# SDA390V1_TASLAK.net
KiCad netlist of a schematic drawn in EAGLE
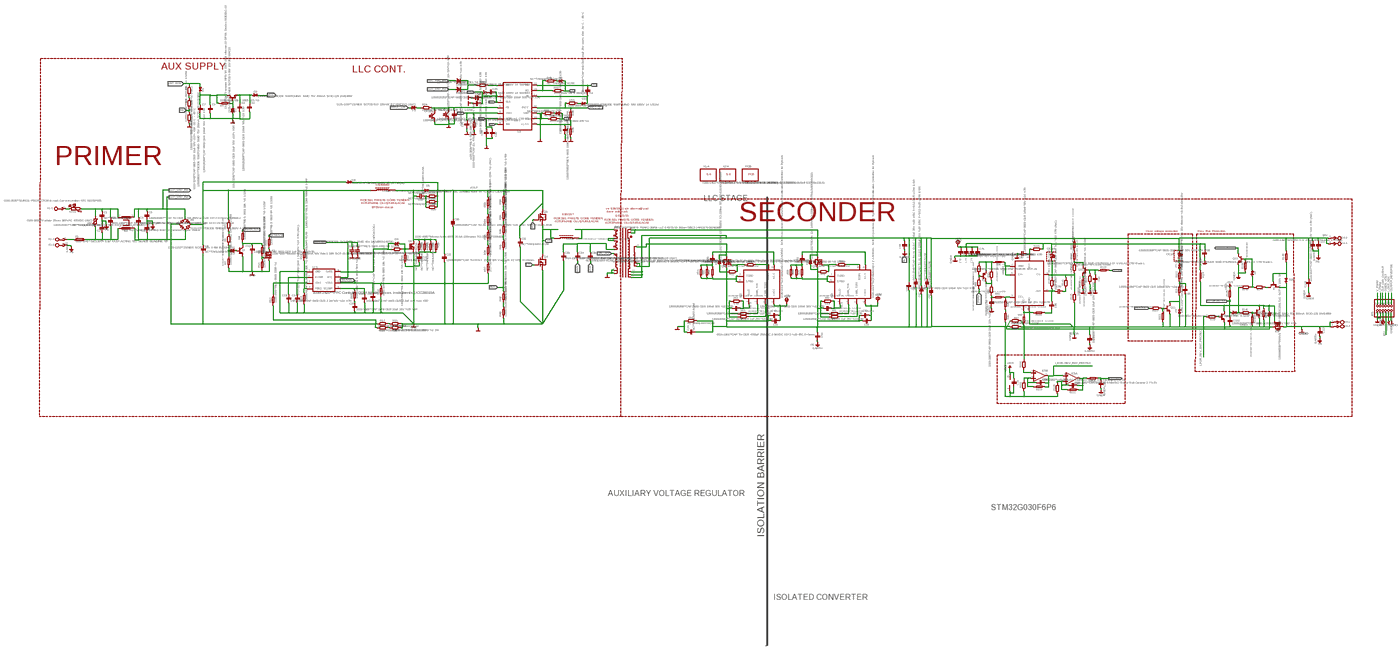
[diagram p0: schematic, sheet 1, overview]
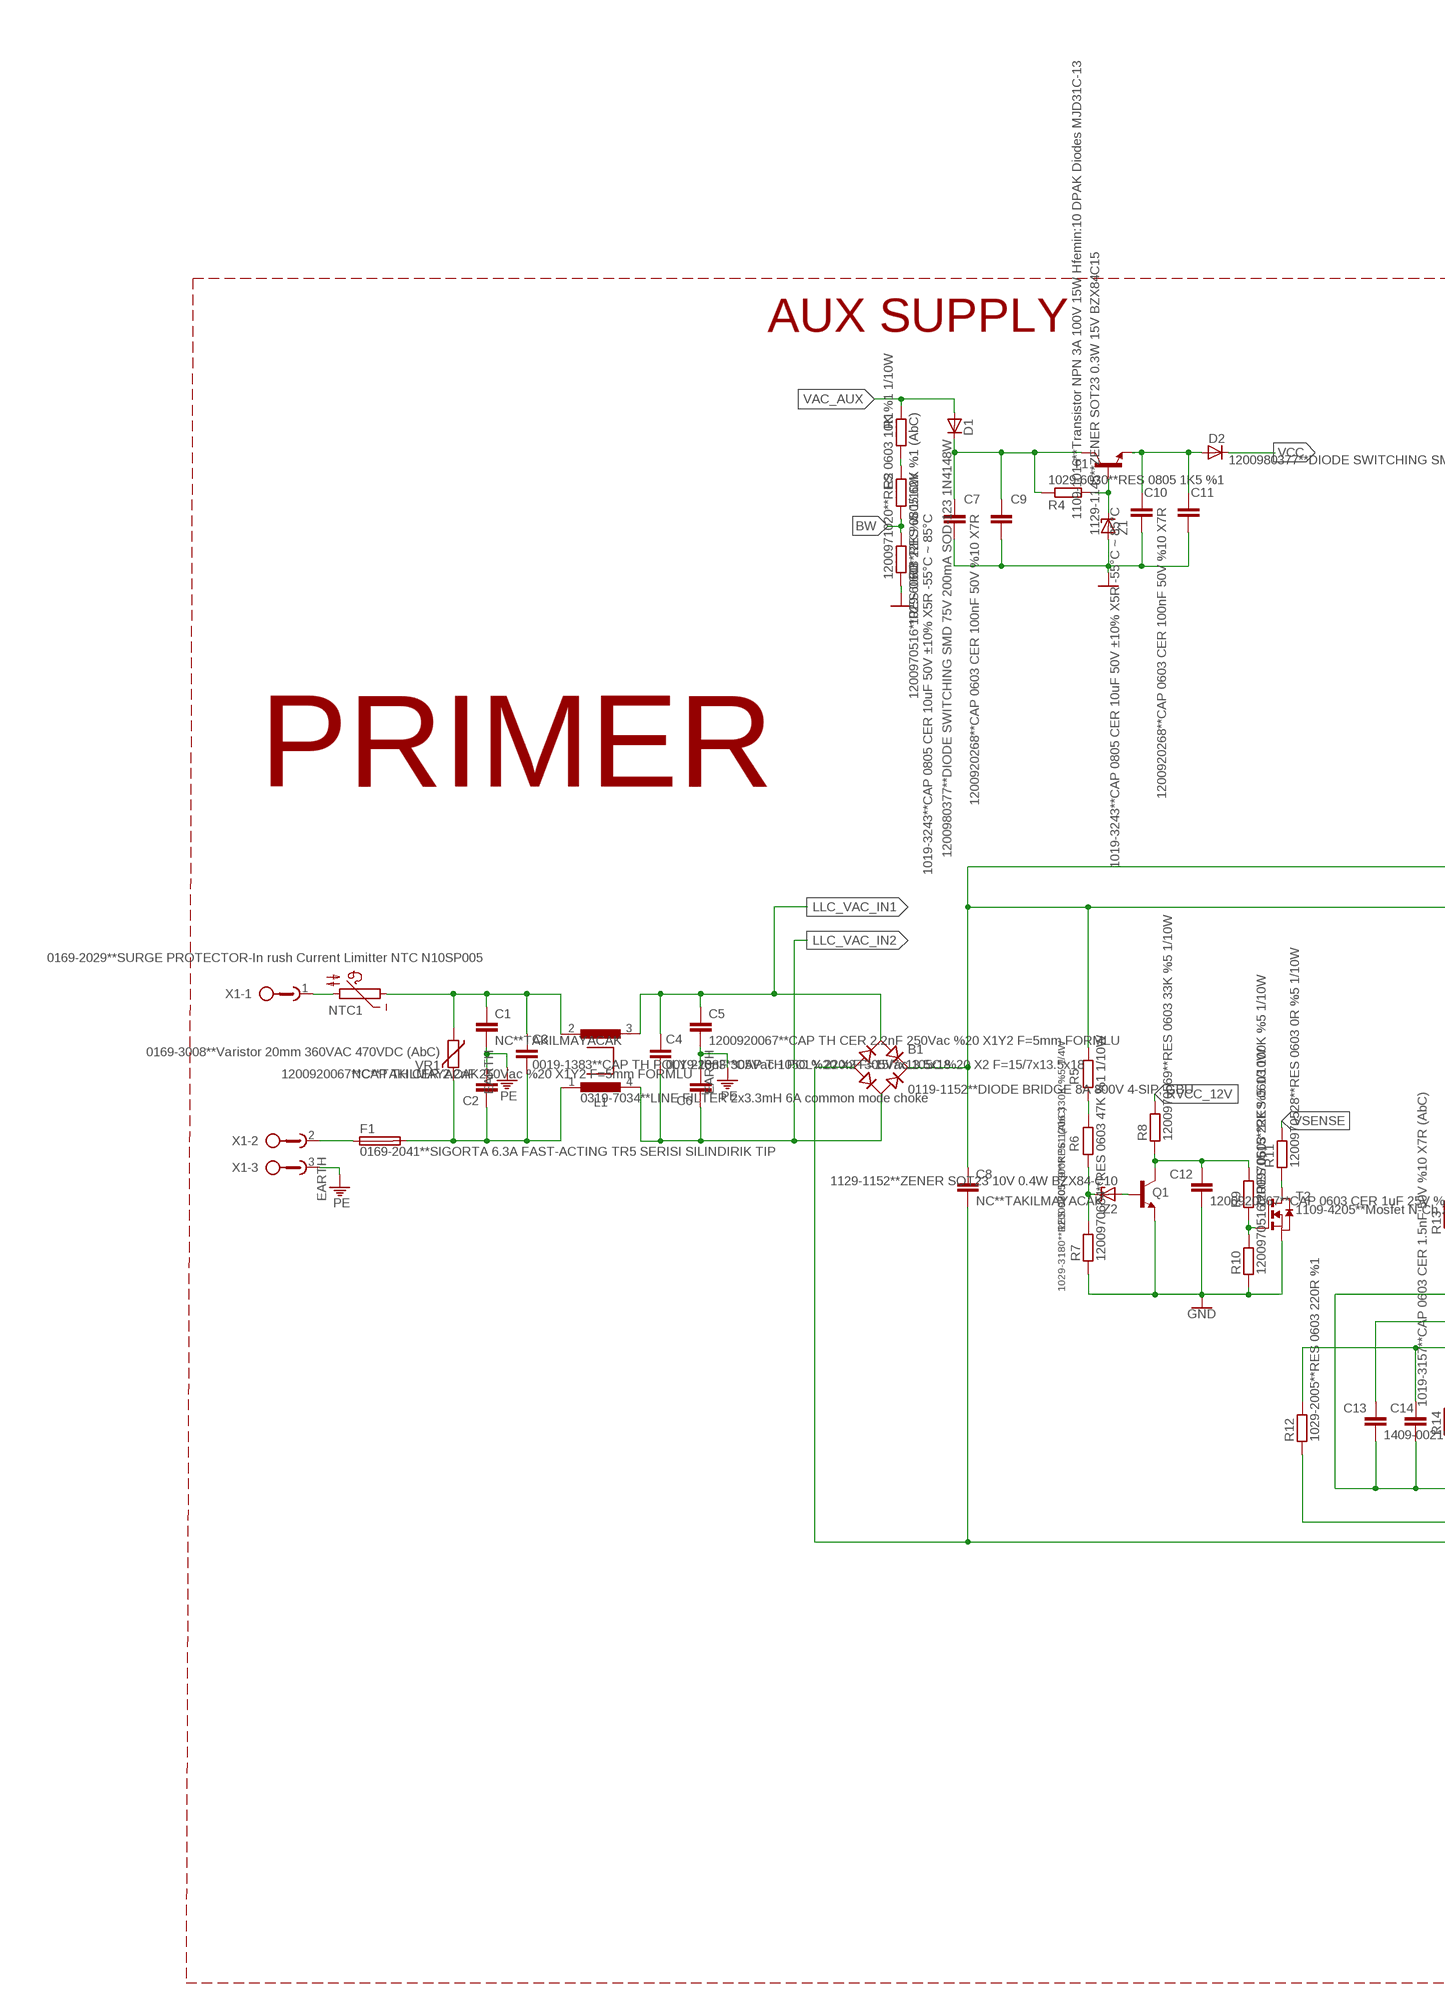
[diagram p1: schematic, sheet 1, part 1 of 4]
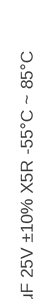
[diagram p2: schematic, sheet 1, part 2 of 4]
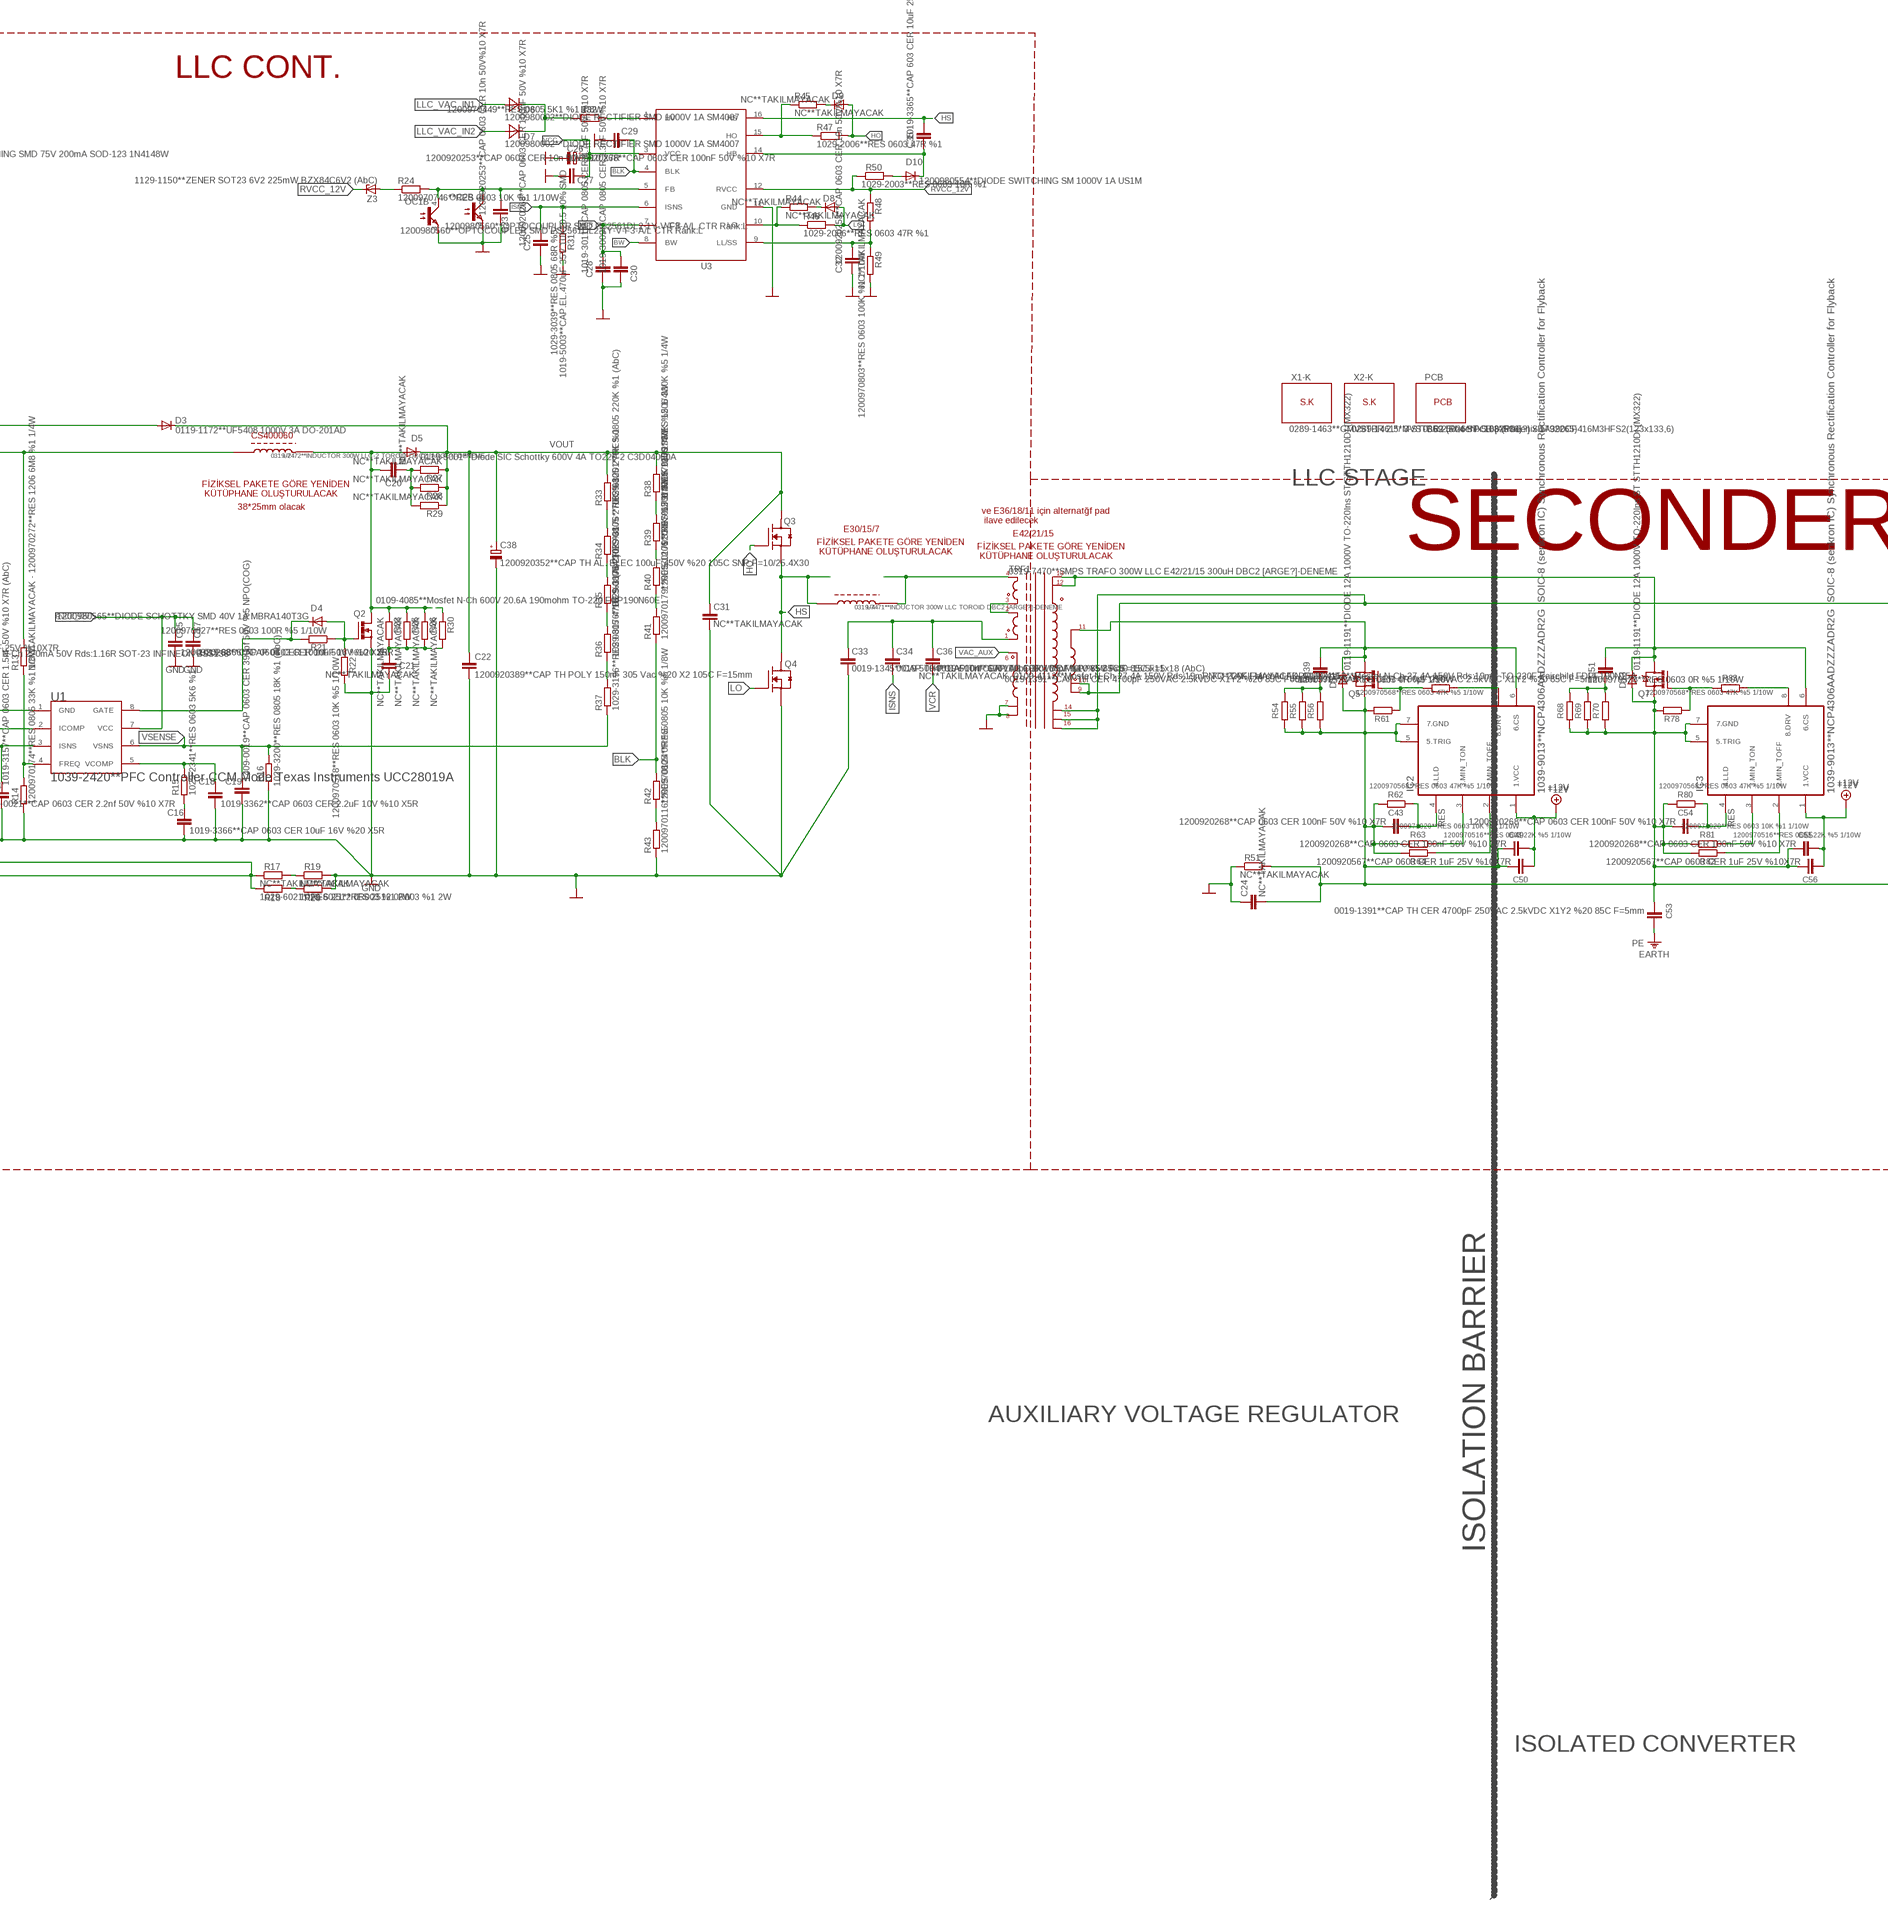
[diagram p3: schematic, sheet 1, part 3 of 4]
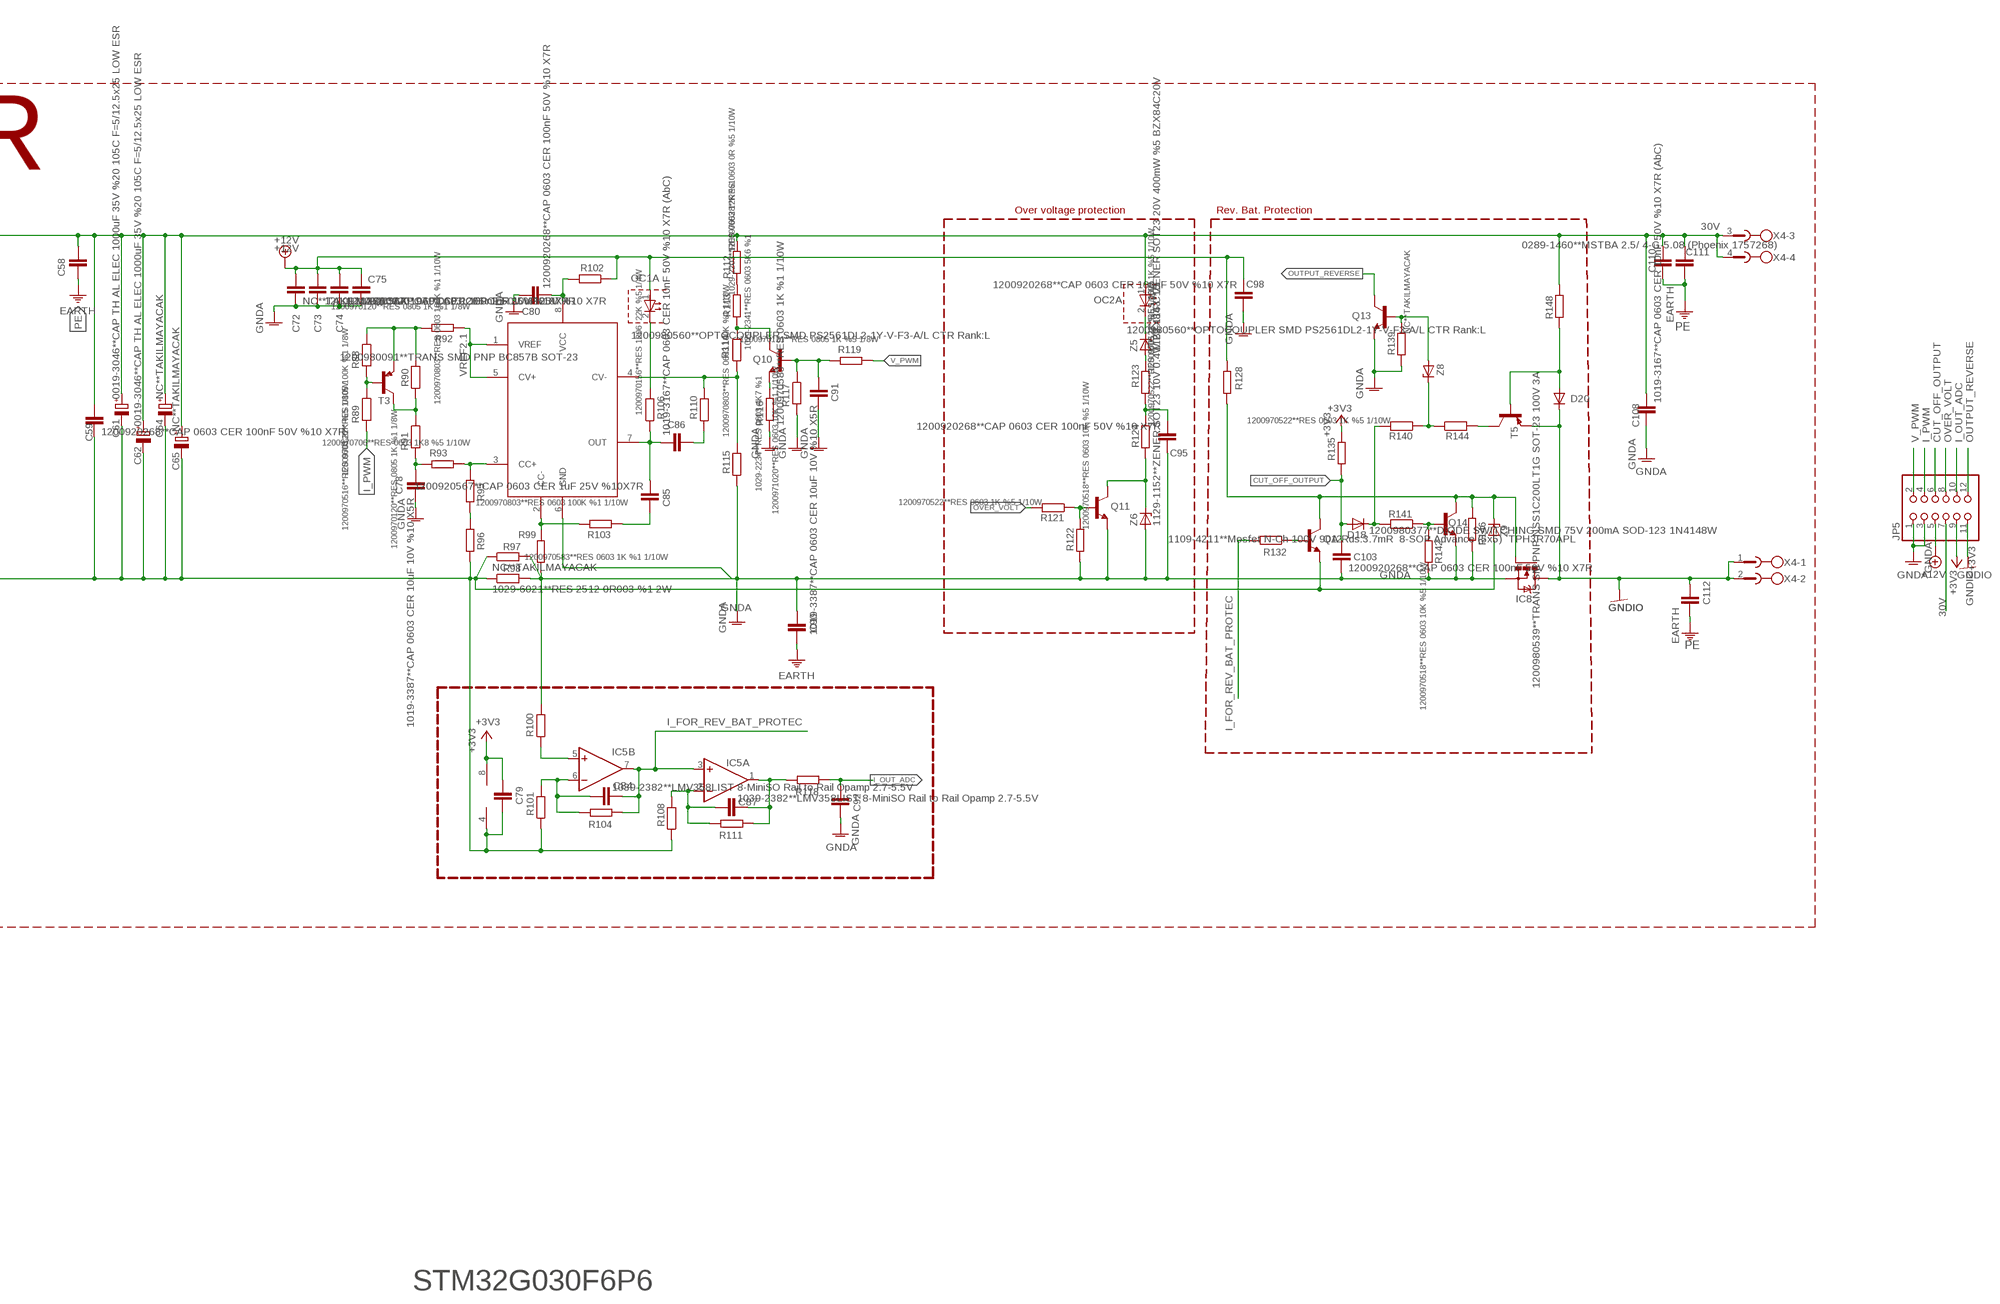
[diagram p4: schematic, sheet 1, part 4 of 4]

(export (version "E")
  (design (tool "Eeschema 10.0.6"))
  (components
    (comp (ref "B1")
      (value "0119-1152**DIODE BRIDGE 8A 800V 4-SIP, GBU")
      (footprint "eagle-import:DıODE_BRIDGE_8A_DIK")
      (libsource (lib "eagle-import") (part "DıODE_BRIDGE_8A_DIK"))
    )
    (comp (ref "C1")
      (value "NC**TAKILMAYACAK")
      (footprint "eagle-import:C050-035X075")
      (libsource (lib "eagle-import") (part "C-EU050-035X075"))
    )
    (comp (ref "C2")
      (value "NC**TAKILMAYACAK")
      (footprint "eagle-import:C050-035X075")
      (libsource (lib "eagle-import") (part "C-EU050-035X075"))
    )
    (comp (ref "C3")
      (value "0019-1383**CAP TH POLY 220nF 305Vac 105C %20 X2 F=15/7x13.5x18")
      (footprint "eagle-import:C150-064X183")
      (libsource (lib "eagle-import") (part "C-EU150-064X183"))
    )
    (comp (ref "C4")
      (value "0019-1383**CAP TH POLY 220nF 305Vac 105C %20 X2 F=15/7x13.5x18")
      (footprint "eagle-import:C150-064X183")
      (libsource (lib "eagle-import") (part "C-EU150-064X183"))
    )
    (comp (ref "C5")
      (value "1200920067**CAP TH CER 2.2nF 250Vac %20 X1Y2 F=5mm FORMLU")
      (footprint "eagle-import:C050-035X075")
      (libsource (lib "eagle-import") (part "C-EU050-035X075"))
    )
    (comp (ref "C6")
      (value "1200920067**CAP TH CER 2.2nF 250Vac %20 X1Y2 F=5mm FORMLU")
      (footprint "eagle-import:C050-035X075")
      (libsource (lib "eagle-import") (part "C-EU050-035X075"))
    )
    (comp (ref "C7")
      (value "1019-3243**CAP 0805 CER 10uF 50V ±10% X5R -55°C ~ 85°C")
      (footprint "eagle-import:C0805_ENKO")
      (libsource (lib "eagle-import") (part "C-EUC0805E"))
    )
    (comp (ref "C8")
      (value "NC**TAKILMAYACAK")
      (footprint "eagle-import:C225-087X268")
      (libsource (lib "eagle-import") (part "C-EU225-087X268"))
    )
    (comp (ref "C9")
      (value "1200920268**CAP 0603 CER 100nF 50V %10 X7R")
      (footprint "eagle-import:C0603_ENKO")
      (libsource (lib "eagle-import") (part "C-EUC0603E"))
    )
    (comp (ref "C10")
      (value "1019-3243**CAP 0805 CER 10uF 50V ±10% X5R -55°C ~ 85°C")
      (footprint "eagle-import:C0805_ENKO")
      (libsource (lib "eagle-import") (part "C-EUC0805E"))
    )
    (comp (ref "C11")
      (value "1200920268**CAP 0603 CER 100nF 50V %10 X7R")
      (footprint "eagle-import:C0603_ENKO")
      (libsource (lib "eagle-import") (part "C-EUC0603E"))
    )
    (comp (ref "C12")
      (value "1200920567**CAP 0603 CER 1uF 25V %10X7R")
      (footprint "eagle-import:C0603_ENKO")
      (libsource (lib "eagle-import") (part "C-EUC0603E"))
    )
    (comp (ref "C13")
      (value "1409-0021**CAP 0603 CER 2.2nf 50V %10 X7R")
      (footprint "eagle-import:C0603_ENKO")
      (libsource (lib "eagle-import") (part "C-EUC0603E"))
    )
    (comp (ref "C14")
      (value "1019-3157**CAP 0603 CER 1.5nF 50V %10 X7R (AbC)")
      (footprint "eagle-import:C0603_ENKO")
      (libsource (lib "eagle-import") (part "C-EUC0603E"))
    )
    (comp (ref "C15")
      (value "1200920268**CAP 0603 CER 100nF 50V %10 X7R")
      (footprint "eagle-import:C0603_ENKO")
      (libsource (lib "eagle-import") (part "C-EUC0603E"))
    )
    (comp (ref "C16")
      (value "1019-3366**CAP 0603 CER 10uF 16V %20 X5R")
      (footprint "eagle-import:C0603_ENKO")
      (libsource (lib "eagle-import") (part "C-EUC0603E"))
    )
    (comp (ref "C17")
      (value "1019-3366**CAP 0603 CER 10uF 16V %20 X5R")
      (footprint "eagle-import:C0603_ENKO")
      (libsource (lib "eagle-import") (part "C-EUC0603E"))
    )
    (comp (ref "C18")
      (value "1019-3362**CAP 0603 CER 2.2uF 10V %10 X5R")
      (footprint "eagle-import:C0603_ENKO")
      (libsource (lib "eagle-import") (part "C-EUC0603E"))
    )
    (comp (ref "C19")
      (value "1409-0019**CAP 0603 CER 390pf 50V %5 NPO(COG)")
      (footprint "eagle-import:C0603_ENKO")
      (libsource (lib "eagle-import") (part "C-EUC0603E"))
    )
    (comp (ref "C20")
      (value "NC**TAKILMAYACAK")
      (footprint "eagle-import:C050-030X075")
      (libsource (lib "eagle-import") (part "C-EU050-030X075"))
    )
    (comp (ref "C21")
      (value "NC**TAKILMAYACAK")
      (footprint "eagle-import:C050-030X075")
      (libsource (lib "eagle-import") (part "C-EU050-030X075"))
    )
    (comp (ref "C22")
      (value "1200920389**CAP TH POLY 150nF 305 Vac %20 X2 105C F=15mm")
      (footprint "eagle-import:C150-054X183")
      (libsource (lib "eagle-import") (part "C-EU150-054X183"))
    )
    (comp (ref "C23")
      (value "1200920253**CAP 0603 CER 10n 50V%10 X7R")
      (footprint "eagle-import:C0603_ENKO")
      (libsource (lib "eagle-import") (part "C-EUC0603E"))
    )
    (comp (ref "C24")
      (value "NC**TAKILMAYACAK")
      (footprint "eagle-import:C075-32X103_DEIF")
      (libsource (lib "eagle-import") (part "C075-32X103_DEIF"))
    )
    (comp (ref "C25")
      (value "1200920268**CAP 0603 CER 100nF 50V %10 X7R")
      (footprint "eagle-import:C0603_ENKO")
      (libsource (lib "eagle-import") (part "C-EUC0603E"))
    )
    (comp (ref "C26")
      (value "1019-5003**CAP.EL.470uF 35V 10X10.5 20% SMD")
      (footprint "eagle-import:153CLV-1010")
      (libsource (lib "eagle-import") (part "CPOL-EU153CLV-1010"))
    )
    (comp (ref "C27")
      (value "1200920268**CAP 0603 CER 100nF 50V %10 X7R")
      (footprint "eagle-import:C0603_ENKO")
      (libsource (lib "eagle-import") (part "C-EUC0603E"))
    )
    (comp (ref "C28")
      (value "1019-3011**CAP 0805 CER 4.7nF 50V %10 X7R")
      (footprint "eagle-import:C0603_ENKO")
      (libsource (lib "eagle-import") (part "C-EUC0603E"))
    )
    (comp (ref "C29")
      (value "1200920253**CAP 0603 CER 10n 50V%10 X7R")
      (footprint "eagle-import:C0603_ENKO")
      (libsource (lib "eagle-import") (part "C-EUC0603E"))
    )
    (comp (ref "C30")
      (value "1019-3009**CAP 0805 CER 3.3nF 50V %10 X7R")
      (footprint "eagle-import:C0603_ENKO")
      (libsource (lib "eagle-import") (part "C-EUC0603E"))
    )
    (comp (ref "C31")
      (value "NC**TAKILMAYACAK")
      (footprint "eagle-import:C150-064X183")
      (libsource (lib "eagle-import") (part "C-EU150-064X183"))
    )
    (comp (ref "C32")
      (value "1200920253**CAP 0603 CER 10n 50V%10 X7R")
      (footprint "eagle-import:C0603_ENKO")
      (libsource (lib "eagle-import") (part "C-EUC0603E"))
    )
    (comp (ref "C33")
      (value "0019-1345**CAP TH POLY 10nF 600VAC 1000VDC MKP %5 85C F=15/5x11x18 (AbC)")
      (footprint "eagle-import:C150-072X183")
      (libsource (lib "eagle-import") (part "C-EU150-072X183"))
    )
    (comp (ref "C34")
      (value "0019-5004**CAP TH CER 100pF 1kV Y5V %10 85C F=5")
      (footprint "eagle-import:C050-055X075")
      (libsource (lib "eagle-import") (part "C-EU050-055X075"))
    )
    (comp (ref "C35")
      (value "1019-3365**CAP 603 CER 10uF 25V ±10% X5R -55°C ~ 85°C")
      (footprint "eagle-import:C0603_ENKO")
      (libsource (lib "eagle-import") (part "C-EUC0603E"))
    )
    (comp (ref "C36")
      (value "0019-5004**CAP TH CER 100pF 1kV Y5V %10 85C F=5")
      (footprint "eagle-import:C050-050X075")
      (libsource (lib "eagle-import") (part "C-EU050-050X075"))
    )
    (comp (ref "C38")
      (value "1200920352**CAP TH AL. ELEC 100uF 450V %20 105C SNP F=10/25.4X30")
      (footprint "eagle-import:EB25D")
      (libsource (lib "eagle-import") (part "CPOL-EUE10-25"))
    )
    (comp (ref "C39")
      (value "0019-1391**CAP TH CER 4700pF 250VAC 2.5kVDC X1Y2 %20 85C F=5mm")
      (footprint "eagle-import:C050-045X075")
      (libsource (lib "eagle-import") (part "C-EU050-045X075"))
    )
    (comp (ref "C43")
      (value "1200920268**CAP 0603 CER 100nF 50V %10 X7R")
      (footprint "eagle-import:C0603_ENKO")
      (libsource (lib "eagle-import") (part "C-EUC0603E"))
    )
    (comp (ref "C49")
      (value "1200920268**CAP 0603 CER 100nF 50V %10 X7R")
      (footprint "eagle-import:C0603_ENKO")
      (libsource (lib "eagle-import") (part "C-EUC0603E"))
    )
    (comp (ref "C50")
      (value "1200920567**CAP 0603 CER 1uF 25V %10X7R")
      (footprint "eagle-import:C0603_ENKO")
      (libsource (lib "eagle-import") (part "C-EUC0603E"))
    )
    (comp (ref "C51")
      (value "0019-1391**CAP TH CER 4700pF 250VAC 2.5kVDC X1Y2 %20 85C F=5mm")
      (footprint "eagle-import:C050-045X075")
      (libsource (lib "eagle-import") (part "C-EU050-045X075"))
    )
    (comp (ref "C53")
      (value "0019-1391**CAP TH CER 4700pF 250VAC 2.5kVDC X1Y2 %20 85C F=5mm")
      (footprint "eagle-import:C050-045X075")
      (libsource (lib "eagle-import") (part "C-EU050-045X075"))
    )
    (comp (ref "C54")
      (value "1200920268**CAP 0603 CER 100nF 50V %10 X7R")
      (footprint "eagle-import:C0603_ENKO")
      (libsource (lib "eagle-import") (part "C-EUC0603E"))
    )
    (comp (ref "C55")
      (value "1200920268**CAP 0603 CER 100nF 50V %10 X7R")
      (footprint "eagle-import:C0603_ENKO")
      (libsource (lib "eagle-import") (part "C-EUC0603E"))
    )
    (comp (ref "C56")
      (value "1200920567**CAP 0603 CER 1uF 25V %10X7R")
      (footprint "eagle-import:C0603_ENKO")
      (libsource (lib "eagle-import") (part "C-EUC0603E"))
    )
    (comp (ref "C58")
      (value "1200920292**CAP TH CER 2.2nF 300Vac %20 X1Y2 F=7.5mm DxS(13x5)")
      (footprint "eagle-import:C075-32X103_C050-035X75")
      (libsource (lib "eagle-import") (part "C075-32X103/C050-035X75"))
    )
    (comp (ref "C59")
      (value "1200920268**CAP 0603 CER 100nF 50V %10 X7R")
      (footprint "eagle-import:C0603_ENKO")
      (libsource (lib "eagle-import") (part "C-EUC0603E"))
    )
    (comp (ref "C61")
      (value "0019-3046**CAP TH AL ELEC 1000uF 35V %20 105C F=5/12.5x25 LOW ESR")
      (footprint "eagle-import:E5-13_E7,5-16")
      (libsource (lib "eagle-import") (part "E5-13/E7,5-16"))
    )
    (comp (ref "C62")
      (value "0019-3046**CAP TH AL ELEC 1000uF 35V %20 105C F=5/12.5x25 LOW ESR")
      (footprint "eagle-import:E5-13_E7,5-16")
      (libsource (lib "eagle-import") (part "E5-13/E7,5-16"))
    )
    (comp (ref "C64")
      (value "NC**TAKILMAYACAK")
      (footprint "eagle-import:E5-13_E7,5-16")
      (libsource (lib "eagle-import") (part "E5-13/E7,5-16"))
    )
    (comp (ref "C65")
      (value "NC**TAKILMAYACAK")
      (footprint "eagle-import:E5-13_E7,5-16")
      (libsource (lib "eagle-import") (part "E5-13/E7,5-16"))
    )
    (comp (ref "C72")
      (value "NC**TAKILMAYACAK")
      (footprint "eagle-import:C0603_ENKO")
      (libsource (lib "eagle-import") (part "C-EUC0603E"))
    )
    (comp (ref "C73")
      (value "1200920268**CAP 0603 CER 100nF 50V %10 X7R")
      (footprint "eagle-import:C0603_ENKO")
      (libsource (lib "eagle-import") (part "C-EUC0603E"))
    )
    (comp (ref "C74")
      (value "1200920567**CAP 0603 CER 1uF 25V %10X7R")
      (footprint "eagle-import:C0603_ENKO")
      (libsource (lib "eagle-import") (part "C-EUC0603E"))
    )
    (comp (ref "C75")
      (value "1200920197**CAP 1206 CER 10uF 25V %10 X7R")
      (footprint "eagle-import:C1206_ENKO")
      (libsource (lib "eagle-import") (part "C-EUC1206E"))
    )
    (comp (ref "C78")
      (value "1019-3387**CAP 0603 CER 10uF 10V %10 X5R")
      (footprint "eagle-import:C0603_ENKO")
      (libsource (lib "eagle-import") (part "C-EUC0603E"))
    )
    (comp (ref "C79")
      (value "1200920268**CAP 0603 CER 100nF 50V %10 X7R")
      (footprint "eagle-import:C0603_ENKO")
      (libsource (lib "eagle-import") (part "C-EUC0603E"))
    )
    (comp (ref "C80")
      (value "1200920268**CAP 0603 CER 100nF 50V %10 X7R")
      (footprint "eagle-import:C0603_ENKO")
      (libsource (lib "eagle-import") (part "C-EUC0603E"))
    )
    (comp (ref "C84")
      (value "NC**TAKILMAYACAK (Not Fitted)")
      (footprint "eagle-import:C0603_ENKO")
      (libsource (lib "eagle-import") (part "C-EUC0603E"))
    )
    (comp (ref "C85")
      (value "1200920567**CAP 0603 CER 1uF 25V %10X7R")
      (footprint "eagle-import:C0603_ENKO")
      (libsource (lib "eagle-import") (part "C-EUC0603E"))
    )
    (comp (ref "C86")
      (value "1019-3167**CAP 0603 CER 10nF 50V %10 X7R (AbC)")
      (footprint "eagle-import:C0603_ENKO")
      (libsource (lib "eagle-import") (part "C-EUC0603E"))
    )
    (comp (ref "C87")
      (value "1200920371**CAP 0603 CER 150p 50V%5 COG")
      (footprint "eagle-import:C0603_ENKO")
      (libsource (lib "eagle-import") (part "C-EUC0603E"))
    )
    (comp (ref "C90")
      (value "NC**TAKILMAYACAK (Not Fitted)")
      (footprint "eagle-import:C050-035X075")
      (libsource (lib "eagle-import") (part "C-EU050-035X075"))
    )
    (comp (ref "C91")
      (value "1019-3387**CAP 0603 CER 10uF 10V %10 X5R")
      (footprint "eagle-import:C0603_ENKO")
      (libsource (lib "eagle-import") (part "C-EUC0603E"))
    )
    (comp (ref "C92")
      (value "1200920268**CAP 0603 CER 100nF 50V %10 X7R")
      (footprint "eagle-import:C0603_ENKO")
      (libsource (lib "eagle-import") (part "C-EUC0603E"))
    )
    (comp (ref "C95")
      (value "1200920268**CAP 0603 CER 100nF 50V %10 X7R")
      (footprint "eagle-import:C0603_ENKO")
      (libsource (lib "eagle-import") (part "C-EUC0603E"))
    )
    (comp (ref "C98")
      (value "1200920268**CAP 0603 CER 100nF 50V %10 X7R")
      (footprint "eagle-import:C0603_ENKO")
      (libsource (lib "eagle-import") (part "C-EUC0603E"))
    )
    (comp (ref "C103")
      (value "1200920268**CAP 0603 CER 100nF 50V %10 X7R")
      (footprint "eagle-import:C0603_ENKO")
      (libsource (lib "eagle-import") (part "C-EUC0603E"))
    )
    (comp (ref "C108")
      (value "1019-3167**CAP 0603 CER 10nF 50V %10 X7R (AbC)")
      (footprint "eagle-import:C0603_ENKO")
      (libsource (lib "eagle-import") (part "C-EUC0603E"))
    )
    (comp (ref "C110")
      (value "0019-1391**CAP TH CER 4700pF 250VAC 2.5kVDC X1Y2 %20 85C F=5mm")
      (footprint "eagle-import:C050-035X075")
      (libsource (lib "eagle-import") (part "C-EU050-035X075"))
    )
    (comp (ref "C111")
      (value "0019-1391**CAP TH CER 4700pF 250VAC 2.5kVDC X1Y2 %20 85C F=5mm")
      (footprint "eagle-import:C050-035X075")
      (libsource (lib "eagle-import") (part "C-EU050-035X075"))
    )
    (comp (ref "C112")
      (value "0019-1391**CAP TH CER 4700pF 250VAC 2.5kVDC X1Y2 %20 85C F=5mm")
      (footprint "eagle-import:C050-035X075")
      (libsource (lib "eagle-import") (part "C-EU050-035X075"))
    )
    (comp (ref "D1")
      (value "1200980377**DIODE SWITCHING SMD 75V 200mA SOD-123 1N4148W")
      (footprint "eagle-import:SOD123")
      (libsource (lib "eagle-import") (part "DIODE-SOD123"))
    )
    (comp (ref "D2")
      (value "1200980377**DIODE SWITCHING SMD 75V 200mA SOD-123 1N4148W")
      (footprint "eagle-import:SOD123")
      (libsource (lib "eagle-import") (part "DIODE-SOD123"))
    )
    (comp (ref "D3")
      (value "0119-1172**UF5408 1000V 3A DO-201AD")
      (footprint "eagle-import:DIODE_D0201-23")
      (libsource (lib "eagle-import") (part "DIODE_D0201-23"))
    )
    (comp (ref "D4")
      (value "1200980565**DIODE SCHOTTKY SMD 40V 1A MBRA140T3G")
      (footprint "eagle-import:SOD106-R")
      (libsource (lib "eagle-import") (part "DIODE-SOD106-R"))
    )
    (comp (ref "D5")
      (value "0119-5001**Diode SIC Schottky 600V 4A TO220-2 C3D04060A")
      (footprint "eagle-import:DIODE_12A_1000V_TO220")
      (libsource (lib "eagle-import") (part "DIODE_12A_1000V_TO220"))
    )
    (comp (ref "D6")
      (value "1200980002**DIODE RECTIFIER SMD 1000V 1A SM4007")
      (footprint "eagle-import:M7_DC_DIYOT")
      (libsource (lib "eagle-import") (part "M7_DC_DIYOT"))
    )
    (comp (ref "D7")
      (value "1200980002**DIODE RECTIFIER SMD 1000V 1A SM4007")
      (footprint "eagle-import:M7_DC_DIYOT")
      (libsource (lib "eagle-import") (part "M7_DC_DIYOT"))
    )
    (comp (ref "D8")
      (value "NC**TAKILMAYACAK")
      (footprint "eagle-import:SOD106-R")
      (libsource (lib "eagle-import") (part "DIODE-SOD106-R"))
    )
    (comp (ref "D9")
      (value "NC**TAKILMAYACAK")
      (footprint "eagle-import:SOD106-R")
      (libsource (lib "eagle-import") (part "DIODE-SOD106-R"))
    )
    (comp (ref "D10")
      (value "1200980554**DIODE SWITCHING SM 1000V 1A US1M")
      (footprint "eagle-import:SOD106-R")
      (libsource (lib "eagle-import") (part "DIODE-SOD106-R"))
    )
    (comp (ref "D11")
      (value "0119-1191**DIODE 12A 1000V TO-220Ins ST STTH1210DI (MX322)")
      (footprint "eagle-import:TO220ACS")
      (libsource (lib "eagle-import") (part "BYW80"))
    )
    (comp (ref "D13")
      (value "0119-1191**DIODE 12A 1000V TO-220Ins ST STTH1210DI (MX322)")
      (footprint "eagle-import:TO220ACS")
      (libsource (lib "eagle-import") (part "BYW80"))
    )
    (comp (ref "D18")
      (value "1200980377**DIODE SWITCHING SMD 75V 200mA SOD-123 1N4148W")
      (footprint "eagle-import:SOD123")
      (libsource (lib "eagle-import") (part "DIODE-SOD123"))
    )
    (comp (ref "D20")
      (value "1200980377**DIODE SWITCHING SMD 75V 200mA SOD-123 1N4148W")
      (footprint "eagle-import:SOD123")
      (libsource (lib "eagle-import") (part "DIODE-SOD123"))
    )
    (comp (ref "F1")
      (value "0169-2041**SIGORTA 6.3A FAST-ACTING TR5 SERISI SILINDIRIK TIP")
      (footprint "eagle-import:19560")
      (fields (field (name "MPN") "56000001009"))
      (libsource (lib "eagle-import") (part "19560"))
    )
    (comp (ref "IC2")
      (value "1039-9013**NCP4306AADZZZADR2G SOIC-8 (senkron IC) Synchronous Rectification Controller for Flyback")
      (footprint "eagle-import:NCP4306")
      (libsource (lib "eagle-import") (part "NCP4306"))
    )
    (comp (ref "IC3")
      (value "1039-9013**NCP4306AADZZZADR2G SOIC-8 (senkron IC) Synchronous Rectification Controller for Flyback")
      (footprint "eagle-import:NCP4306")
      (libsource (lib "eagle-import") (part "NCP4306"))
    )
    (comp (ref "IC4")
      (value "1039-2224**TSM1011ID SO-8 Constant Voltage and Constant Current Controller")
      (footprint "eagle-import:SO-8")
      (libsource (lib "eagle-import") (part "TSM1011"))
    )
    (comp (ref "IC5")
      (value "1039-2382**LMV358LIST 8-MiniSO Rail to Rail Opamp 2.7-5.5V")
      (footprint "eagle-import:MSOP08")
      (libsource (lib "eagle-import") (part "LMV358?MM"))
    )
    (comp (ref "IC8")
      (value "1109-4211**Mosfet N-Ch 100V 90A Rds:3.7mR 8-SOP Advance (5x5) TPH3R70APL")
      (footprint "eagle-import:TPH6R30ANL")
      (libsource (lib "eagle-import") (part "TPH6R30ANL"))
    )
    (comp (ref "JP5")
      (value "PINHD-2X6_2.54")
      (footprint "eagle-import:2X06")
      (libsource (lib "eagle-import") (part "PINHD-2X6_2.54"))
    )
    (comp (ref "L1")
      (value "0319-7034**LINE FILTER 2x3.3mH 6A common mode choke")
      (footprint "eagle-import:EPCOS_B82724J")
      (libsource (lib "eagle-import") (part "EPCOS_B82724J"))
    )
    (comp (ref "NTC1")
      (value "0169-2029**SURGE PROTECTOR-In rush Current Limitter NTC N10SP005")
      (footprint "eagle-import:SENS_NTC")
      (libsource (lib "eagle-import") (part "SENS_NTC"))
    )
    (comp (ref "OC1")
      (value "1200980560**OPTOCOUPLER SMD PS2561DL2-1Y-V-F3-A/L CTR Rank:L")
      (footprint "eagle-import:PS2561DL2-1_OPTO1")
      (libsource (lib "eagle-import") (part "PS2561DL2-1_OPTO1"))
    )
    (comp (ref "OC2")
      (value "1200980560**OPTOCOUPLER SMD PS2561DL2-1Y-V-F3-A/L CTR Rank:L")
      (footprint "eagle-import:PS2561DL2-1_OPTO1")
      (libsource (lib "eagle-import") (part "PS2561DL2-1_OPTO1"))
    )
    (comp (ref "PCB")
      (value "0369-5026**PCB [ARGE?] SDA390CF416M3HFS2(123x133,6)")
      (footprint "eagle-import:PCB")
      (libsource (lib "eagle-import") (part "PCB"))
    )
    (comp (ref "Q1")
      (value "1200980090**TRANS SMD NPN BC847B SOT-23")
      (footprint "eagle-import:SOT23")
      (libsource (lib "eagle-import") (part "BC846SMDALT1"))
    )
    (comp (ref "Q2")
      (value "0109-4085**Mosfet N-Ch 600V 20.6A 190mohm TO-220 FCP190N60E")
      (footprint "eagle-import:TO220BV")
      (libsource (lib "eagle-import") (part "PMOSFET_NTO220BV"))
    )
    (comp (ref "Q3")
      (value "0109-4091**Mosfet N-Ch 800V 9A 0.16R TO-220FP Vishay SIHA24N80AE-GE3")
      (footprint "eagle-import:ISO_TO_220")
      (libsource (lib "eagle-import") (part "ISO_TO_220"))
    )
    (comp (ref "Q4")
      (value "0109-4091**Mosfet N-Ch 800V 9A 0.16R TO-220FP Vishay SIHA24N80AE-GE3")
      (footprint "eagle-import:ISO_TO_220")
      (libsource (lib "eagle-import") (part "ISO_TO_220"))
    )
    (comp (ref "Q5")
      (value "NC**TAKILMAYACAK 0109-4112**Mosfet N-Ch 27.4A 150V Rds:19mR TO-220F Fairchild FDPF190N15A")
      (footprint "eagle-import:TO220BV")
      (libsource (lib "eagle-import") (part "STP5NA50"))
    )
    (comp (ref "Q7")
      (value "NC**TAKILMAYACAK 0109-4112**Mosfet N-Ch 27.4A 150V Rds:19mR TO-220F Fairchild FDPF190N15A")
      (footprint "eagle-import:TO220BV")
      (libsource (lib "eagle-import") (part "STP5NA50"))
    )
    (comp (ref "Q10")
      (value "1200980090**TRANS SMD NPN BC847B SOT-23")
      (footprint "eagle-import:SOT23")
      (libsource (lib "eagle-import") (part "BC846SMDBLT1"))
    )
    (comp (ref "Q11")
      (value "1200980090**TRANS SMD NPN BC847B SOT-23")
      (footprint "eagle-import:SOT23")
      (libsource (lib "eagle-import") (part "BC846SMDALT1"))
    )
    (comp (ref "Q12")
      (value "1200980090**TRANS SMD NPN BC847B SOT-23")
      (footprint "eagle-import:SOT23")
      (libsource (lib "eagle-import") (part "BC846SMDALT1"))
    )
    (comp (ref "Q13")
      (value "NC**TAKILMAYACAK")
      (footprint "eagle-import:SOT23")
      (libsource (lib "eagle-import") (part "BC846SMDALT1"))
    )
    (comp (ref "Q14")
      (value "1200980090**TRANS SMD NPN BC847B SOT-23")
      (footprint "eagle-import:SOT23")
      (libsource (lib "eagle-import") (part "BC846SMDALT1"))
    )
    (comp (ref "R1")
      (value "1029-6060**RES 0805 62K %1 (AbC)")
      (footprint "eagle-import:R0603_ENKO")
      (libsource (lib "eagle-import") (part "R-EU_R0603E"))
    )
    (comp (ref "R2")
      (value "1200970516**RES 0603 22K %5 1/10W")
      (footprint "eagle-import:R0603_ENKO")
      (libsource (lib "eagle-import") (part "R-EU_R0603E"))
    )
    (comp (ref "R3")
      (value "1200971020**RES 0603 10K %1 1/10W")
      (footprint "eagle-import:R0603_ENKO")
      (libsource (lib "eagle-import") (part "R-EU_R0603E"))
    )
    (comp (ref "R4")
      (value "1029-6030**RES 0805 1K5 %1")
      (footprint "eagle-import:R0805_ENKO")
      (libsource (lib "eagle-import") (part "R-EU_R0805E"))
    )
    (comp (ref "R5")
      (value "1200970179**RES 1206 330K %5 1/4W")
      (footprint "eagle-import:R1206_ENKO")
      (libsource (lib "eagle-import") (part "R-EU_R1206E"))
    )
    (comp (ref "R6")
      (value "1029-3180**RES 0805 300K %1 (AbC)")
      (footprint "eagle-import:R1206_ENKO")
      (libsource (lib "eagle-import") (part "R-EU_R1206E"))
    )
    (comp (ref "R7")
      (value "1200970684**RES 0603 47K %1 1/10W")
      (footprint "eagle-import:R0603_ENKO")
      (libsource (lib "eagle-import") (part "R-EU_R0603E"))
    )
    (comp (ref "R8")
      (value "1200970569**RES 0603 33K %5 1/10W")
      (footprint "eagle-import:R0603_ENKO")
      (libsource (lib "eagle-import") (part "R-EU_R0603E"))
    )
    (comp (ref "R9")
      (value "1200970515**RES 0603 100K %5 1/10W")
      (footprint "eagle-import:R0603_ENKO")
      (libsource (lib "eagle-import") (part "R-EU_R0603E"))
    )
    (comp (ref "R10")
      (value "1200970516**RES 0603 22K %5 1/10W")
      (footprint "eagle-import:R0603_ENKO")
      (libsource (lib "eagle-import") (part "R-EU_R0603E"))
    )
    (comp (ref "R11")
      (value "1200970528**RES 0603 0R %5 1/10W")
      (footprint "eagle-import:R0603_ENKO")
      (libsource (lib "eagle-import") (part "R-EU_R0603E"))
    )
    (comp (ref "R12")
      (value "1029-2005**RES 0603 220R %1")
      (footprint "eagle-import:R0603_ENKO")
      (libsource (lib "eagle-import") (part "R-EU_R0603E"))
    )
    (comp (ref "R13")
      (value "NC**TAKILMAYACAK - 1200970272**RES 1206 6M8 %1 1/4W")
      (footprint "eagle-import:R1206_ENKO")
      (libsource (lib "eagle-import") (part "R-EU_R1206E"))
    )
    (comp (ref "R14")
      (value "1200970174**RES 0805 33K %1 1/8W")
      (footprint "eagle-import:R0805_ENKO")
      (libsource (lib "eagle-import") (part "R-EU_R0805E"))
    )
    (comp (ref "R15")
      (value "1029-2341**RES 0603 5K6 %1")
      (footprint "eagle-import:R0603_ENKO")
      (libsource (lib "eagle-import") (part "R-EU_R0603E"))
    )
    (comp (ref "R16")
      (value "1029-3200**RES 0805 18K %1 (AbC)")
      (footprint "eagle-import:R0805_ENKO")
      (libsource (lib "eagle-import") (part "R-EU_R0805E"))
    )
    (comp (ref "R17")
      (value "NC**TAKILMAYACAK")
      (footprint "eagle-import:R2512")
      (libsource (lib "eagle-import") (part "R-EU_R2512"))
    )
    (comp (ref "R18")
      (value "1029-6021**RES 2512 0R003 %1 2W")
      (footprint "eagle-import:R2512")
      (libsource (lib "eagle-import") (part "R-EU_R2512"))
    )
    (comp (ref "R19")
      (value "NC**TAKILMAYACAK")
      (footprint "eagle-import:R2512")
      (libsource (lib "eagle-import") (part "R-EU_R2512"))
    )
    (comp (ref "R20")
      (value "1029-6021**RES 2512 0R003 %1 2W")
      (footprint "eagle-import:R2512")
      (libsource (lib "eagle-import") (part "R-EU_R2512"))
    )
    (comp (ref "R21")
      (value "1200970627**RES 0603 100R %5 1/10W")
      (footprint "eagle-import:R0603_ENKO")
      (libsource (lib "eagle-import") (part "R-EU_R0603E"))
    )
    (comp (ref "R22")
      (value "1200970518**RES 0603 10K %5 1/10W")
      (footprint "eagle-import:R0603_ENKO")
      (libsource (lib "eagle-import") (part "R-EU_R0603E"))
    )
    (comp (ref "R23")
      (value "NC**TAKILMAYACAK")
      (footprint "eagle-import:R1206_ENKO")
      (libsource (lib "eagle-import") (part "R-EU_R1206E"))
    )
    (comp (ref "R24")
      (value "1200970746**RES 0603 10K %1 1/10W")
      (footprint "eagle-import:R0603_ENKO")
      (libsource (lib "eagle-import") (part "R-EU_R0603E"))
    )
    (comp (ref "R25")
      (value "NC**TAKILMAYACAK")
      (footprint "eagle-import:R1206_ENKO")
      (libsource (lib "eagle-import") (part "R-EU_R1206E"))
    )
    (comp (ref "R26")
      (value "NC**TAKILMAYACAK")
      (footprint "eagle-import:R1206_ENKO")
      (libsource (lib "eagle-import") (part "R-EU_R1206E"))
    )
    (comp (ref "R27")
      (value "NC**TAKILMAYACAK")
      (footprint "eagle-import:R1206_ENKO")
      (libsource (lib "eagle-import") (part "R-EU_R1206E"))
    )
    (comp (ref "R28")
      (value "NC**TAKILMAYACAK")
      (footprint "eagle-import:R1206_ENKO")
      (libsource (lib "eagle-import") (part "R-EU_R1206E"))
    )
    (comp (ref "R29")
      (value "NC**TAKILMAYACAK")
      (footprint "eagle-import:R1206_ENKO")
      (libsource (lib "eagle-import") (part "R-EU_R1206E"))
    )
    (comp (ref "R30")
      (value "NC**TAKILMAYACAK")
      (footprint "eagle-import:R1206_ENKO")
      (libsource (lib "eagle-import") (part "R-EU_R1206E"))
    )
    (comp (ref "R31")
      (value "1029-3039**RES 0805 68R %5")
      (footprint "eagle-import:R0603_ENKO")
      (libsource (lib "eagle-import") (part "R-EU_R0603E"))
    )
    (comp (ref "R32")
      (value "1200970449**RES 0805 5K1 %1 1/8W")
      (footprint "eagle-import:R0805_ENKO")
      (libsource (lib "eagle-import") (part "R-EU_R0805E"))
    )
    (comp (ref "R33")
      (value "1029-3201**RES 0805 220K %1 (AbC)")
      (footprint "eagle-import:R0805_ENKO")
      (libsource (lib "eagle-import") (part "R-EU_R0805E"))
    )
    (comp (ref "R34")
      (value "1029-3176**RES 0805 270K %1")
      (footprint "eagle-import:R0805_ENKO")
      (libsource (lib "eagle-import") (part "R-EU_R0805E"))
    )
    (comp (ref "R35")
      (value "1029-3176**RES 0805 270K %1")
      (footprint "eagle-import:R0805_ENKO")
      (libsource (lib "eagle-import") (part "R-EU_R0805E"))
    )
    (comp (ref "R36")
      (value "1029-3176**RES 0805 270K %1")
      (footprint "eagle-import:R0805_ENKO")
      (libsource (lib "eagle-import") (part "R-EU_R0805E"))
    )
    (comp (ref "R37")
      (value "1029-3196**RES 0805 470K %1 (AbC)")
      (footprint "eagle-import:R0805_ENKO")
      (libsource (lib "eagle-import") (part "R-EU_R0805E"))
    )
    (comp (ref "R38")
      (value "1200970179**RES 1206 330K %5 1/4W")
      (footprint "eagle-import:R1206_ENKO")
      (libsource (lib "eagle-import") (part "R-EU_R1206E"))
    )
    (comp (ref "R39")
      (value "1200970179**RES 1206 330K %5 1/4W")
      (footprint "eagle-import:R1206_ENKO")
      (libsource (lib "eagle-import") (part "R-EU_R1206E"))
    )
    (comp (ref "R40")
      (value "1200970179**RES 1206 330K %5 1/4W")
      (footprint "eagle-import:R1206_ENKO")
      (libsource (lib "eagle-import") (part "R-EU_R1206E"))
    )
    (comp (ref "R41")
      (value "1200970179**RES 1206 330K %5 1/4W")
      (footprint "eagle-import:R1206_ENKO")
      (libsource (lib "eagle-import") (part "R-EU_R1206E"))
    )
    (comp (ref "R42")
      (value "1200970124**RES 0805 10K %5 1/8W")
      (footprint "eagle-import:R0805_ENKO")
      (libsource (lib "eagle-import") (part "R-EU_R0805E"))
    )
    (comp (ref "R43")
      (value "1200970116**RES 0805 0R %5")
      (footprint "eagle-import:R0805_ENKO")
      (libsource (lib "eagle-import") (part "R-EU_R0805E"))
    )
    (comp (ref "R44")
      (value "NC**TAKILMAYACAK")
      (footprint "eagle-import:R0603_ENKO")
      (libsource (lib "eagle-import") (part "R-EU_R0603E"))
    )
    (comp (ref "R45")
      (value "NC**TAKILMAYACAK")
      (footprint "eagle-import:R0603_ENKO")
      (libsource (lib "eagle-import") (part "R-EU_R0603E"))
    )
    (comp (ref "R46")
      (value "1029-2006**RES 0603 47R %1")
      (footprint "eagle-import:R0603_ENKO")
      (libsource (lib "eagle-import") (part "R-EU_R0603E"))
    )
    (comp (ref "R47")
      (value "1029-2006**RES 0603 47R %1")
      (footprint "eagle-import:R0603_ENKO")
      (libsource (lib "eagle-import") (part "R-EU_R0603E"))
    )
    (comp (ref "R48")
      (value "NC**TAKILMAYACAK")
      (footprint "eagle-import:R0603_ENKO")
      (libsource (lib "eagle-import") (part "R-EU_R0603E"))
    )
    (comp (ref "R49")
      (value "1200970803**RES 0603 100K %1 1/10W")
      (footprint "eagle-import:R0603_ENKO")
      (libsource (lib "eagle-import") (part "R-EU_R0603E"))
    )
    (comp (ref "R50")
      (value "1029-2003**RES 0603 10R %1")
      (footprint "eagle-import:R0603_ENKO")
      (libsource (lib "eagle-import") (part "R-EU_R0603E"))
    )
    (comp (ref "R51")
      (value "NC**TAKILMAYACAK")
      (footprint "eagle-import:0207_15")
      (libsource (lib "eagle-import") (part "R-EU_0207/15"))
    )
    (comp (ref "R54")
      (value "1029-4045**RES 1206 22R %5")
      (footprint "eagle-import:R1206_ENKO")
      (libsource (lib "eagle-import") (part "R-EU_R1206E"))
    )
    (comp (ref "R55")
      (value "NC**TAKILMAYACAK")
      (footprint "eagle-import:R1206_ENKO")
      (libsource (lib "eagle-import") (part "R-EU_R1206E"))
    )
    (comp (ref "R56")
      (value "1029-4045**RES 1206 22R %5")
      (footprint "eagle-import:R1206_ENKO")
      (libsource (lib "eagle-import") (part "R-EU_R1206E"))
    )
    (comp (ref "R61")
      (value "1200970568**RES 0603 47K %5 1/10W")
      (footprint "eagle-import:R0603_ENKO")
      (libsource (lib "eagle-import") (part "R-EU_R0603E"))
    )
    (comp (ref "R62")
      (value "1200970568**RES 0603 47K %5 1/10W")
      (footprint "eagle-import:R0603_ENKO")
      (libsource (lib "eagle-import") (part "R-EU_R0603E"))
    )
    (comp (ref "R63")
      (value "1200971020**RES 0603 10K %1 1/10W")
      (footprint "eagle-import:R0603_ENKO")
      (libsource (lib "eagle-import") (part "R-EU_R0603E"))
    )
    (comp (ref "R64")
      (value "1200970516**RES 0603 22K %5 1/10W")
      (footprint "eagle-import:R0603_ENKO")
      (libsource (lib "eagle-import") (part "R-EU_R0603E"))
    )
    (comp (ref "R65")
      (value "1200970528**RES 0603 0R %5 1/10W")
      (footprint "eagle-import:R0603_ENKO")
      (libsource (lib "eagle-import") (part "R-EU_R0603E"))
    )
    (comp (ref "R68")
      (value "1029-4045**RES 1206 22R %5")
      (footprint "eagle-import:R1206_ENKO")
      (libsource (lib "eagle-import") (part "R-EU_R1206E"))
    )
    (comp (ref "R69")
      (value "NC**TAKILMAYACAK")
      (footprint "eagle-import:R1206_ENKO")
      (libsource (lib "eagle-import") (part "R-EU_R1206E"))
    )
    (comp (ref "R70")
      (value "1029-4045**RES 1206 22R %5")
      (footprint "eagle-import:R1206_ENKO")
      (libsource (lib "eagle-import") (part "R-EU_R1206E"))
    )
    (comp (ref "R78")
      (value "1200970568**RES 0603 47K %5 1/10W")
      (footprint "eagle-import:R0603_ENKO")
      (libsource (lib "eagle-import") (part "R-EU_R0603E"))
    )
    (comp (ref "R80")
      (value "1200970568**RES 0603 47K %5 1/10W")
      (footprint "eagle-import:R0603_ENKO")
      (libsource (lib "eagle-import") (part "R-EU_R0603E"))
    )
    (comp (ref "R81")
      (value "1200971020**RES 0603 10K %1 1/10W")
      (footprint "eagle-import:R0603_ENKO")
      (libsource (lib "eagle-import") (part "R-EU_R0603E"))
    )
    (comp (ref "R82")
      (value "1200970516**RES 0603 22K %5 1/10W")
      (footprint "eagle-import:R0603_ENKO")
      (libsource (lib "eagle-import") (part "R-EU_R0603E"))
    )
    (comp (ref "R83")
      (value "1200970528**RES 0603 0R %5 1/10W")
      (footprint "eagle-import:R0603_ENKO")
      (libsource (lib "eagle-import") (part "R-EU_R0603E"))
    )
    (comp (ref "R88")
      (value "1200970126**RES 0805 100K %1 1/8W")
      (footprint "eagle-import:R0805_ENKO")
      (libsource (lib "eagle-import") (part "R-EU_R0805E"))
    )
    (comp (ref "R89")
      (value "1200970516**RES 0603 22K %5 1/10W")
      (footprint "eagle-import:R0603_ENKO")
      (libsource (lib "eagle-import") (part "R-EU_R0603E"))
    )
    (comp (ref "R90")
      (value "1200970803**RES 0603 100K %1 1/10W")
      (footprint "eagle-import:R0603_ENKO")
      (libsource (lib "eagle-import") (part "R-EU_R0603E"))
    )
    (comp (ref "R91")
      (value "1200970120**RES 0805 1K %1 1/8W")
      (footprint "eagle-import:R0805_ENKO")
      (libsource (lib "eagle-import") (part "R-EU_R0805E"))
    )
    (comp (ref "R92")
      (value "1200970120**RES 0805 1K %1 1/8W")
      (footprint "eagle-import:R0805_ENKO")
      (libsource (lib "eagle-import") (part "R-EU_R0805E"))
    )
    (comp (ref "R93")
      (value "1200970706**RES 0603 1K8 %5 1/10W")
      (footprint "eagle-import:R0603_ENKO")
      (libsource (lib "eagle-import") (part "R-EU_R0603E"))
    )
    (comp (ref "R95")
      (value "1029-2003**RES 0603 10R %1")
      (footprint "eagle-import:R0603_ENKO")
      (libsource (lib "eagle-import") (part "R-EU_R0603E"))
    )
    (comp (ref "R96")
      (value "1029-3416**RES 0805 47R %1 (AbC) (MX322)")
      (footprint "eagle-import:R0805_ENKO")
      (libsource (lib "eagle-import") (part "R-EU_R0805E"))
    )
    (comp (ref "R97")
      (value "NC**TAKILMAYACAK")
      (footprint "eagle-import:R2512")
      (libsource (lib "eagle-import") (part "R-EU_R2512"))
    )
    (comp (ref "R98")
      (value "1029-6021**RES 2512 0R003 %1 2W")
      (footprint "eagle-import:R2512")
      (libsource (lib "eagle-import") (part "R-EU_R2512"))
    )
    (comp (ref "R99")
      (value "1200970583**RES 0603 1K %1 1/10W")
      (footprint "eagle-import:R0603_ENKO")
      (libsource (lib "eagle-import") (part "R-EU_R0603E"))
    )
    (comp (ref "R100")
      (value "1200970522**RES 0603 1K %5 1/10W")
      (footprint "eagle-import:R0603_ENKO")
      (libsource (lib "eagle-import") (part "R-EU_R0603E"))
    )
    (comp (ref "R101")
      (value "1200970522**RES 0603 1K %5 1/10W")
      (footprint "eagle-import:R0603_ENKO")
      (libsource (lib "eagle-import") (part "R-EU_R0603E"))
    )
    (comp (ref "R102")
      (value "1029-2003**RES 0603 10R %1")
      (footprint "eagle-import:R0603_ENKO")
      (libsource (lib "eagle-import") (part "R-EU_R0603E"))
    )
    (comp (ref "R103")
      (value "1200970803**RES 0603 100K %1 1/10W")
      (footprint "eagle-import:R0603_ENKO")
      (libsource (lib "eagle-import") (part "R-EU_R0603E"))
    )
    (comp (ref "R104")
      (value "1029-2234**RES 0603 4K7 %1")
      (footprint "eagle-import:R0603_ENKO")
      (libsource (lib "eagle-import") (part "R-EU_R0603E"))
    )
    (comp (ref "R106")
      (value "1200970156**RES 1206 22K %5 1/4W")
      (footprint "eagle-import:R1206_ENKO")
      (libsource (lib "eagle-import") (part "R-EU_R1206E"))
    )
    (comp (ref "R108")
      (value "1200970583**RES 0603 1K %1 1/10W")
      (footprint "eagle-import:R0603_ENKO")
      (libsource (lib "eagle-import") (part "R-EU_R0603E"))
    )
    (comp (ref "R110")
      (value "1200970803**RES 0603 100K %1 1/10W")
      (footprint "eagle-import:R0603_ENKO")
      (libsource (lib "eagle-import") (part "R-EU_R0603E"))
    )
    (comp (ref "R111")
      (value "1029-6089**RES 0603 6K8 %5")
      (footprint "eagle-import:R0603_ENKO")
      (libsource (lib "eagle-import") (part "R-EU_R0603E"))
    )
    (comp (ref "R112")
      (value "1200970528**RES 0603 0R %5 1/10W")
      (footprint "eagle-import:R0603_ENKO")
      (libsource (lib "eagle-import") (part "R-EU_R0603E"))
    )
    (comp (ref "R113")
      (value "1029-2203**RES 0603 12K %1")
      (footprint "eagle-import:R0603_ENKO")
      (libsource (lib "eagle-import") (part "R-EU_R0603E"))
    )
    (comp (ref "R114")
      (value "1029-2341**RES 0603 5K6 %1")
      (footprint "eagle-import:R0603_ENKO")
      (libsource (lib "eagle-import") (part "R-EU_R0603E"))
    )
    (comp (ref "R115")
      (value "1029-2234**RES 0603 4K7 %1")
      (footprint "eagle-import:R0603_ENKO")
      (libsource (lib "eagle-import") (part "R-EU_R0603E"))
    )
    (comp (ref "R116")
      (value "1200970583**RES 0603 1K %1 1/10W")
      (footprint "eagle-import:R0603_ENKO")
      (libsource (lib "eagle-import") (part "R-EU_R0603E"))
    )
    (comp (ref "R117")
      (value "1200971020**RES 0603 10K %1 1/10W")
      (footprint "eagle-import:R0603_ENKO")
      (libsource (lib "eagle-import") (part "R-EU_R0603E"))
    )
    (comp (ref "R118")
      (value "1200970522**RES 0603 1K %5 1/10W")
      (footprint "eagle-import:R0603_ENKO")
      (libsource (lib "eagle-import") (part "R-EU_R0603E"))
    )
    (comp (ref "R119")
      (value "1200970121**RES 0805 1K %5 1/8W")
      (footprint "eagle-import:R0805_ENKO")
      (libsource (lib "eagle-import") (part "R-EU_R0805E"))
    )
    (comp (ref "R121")
      (value "1200970522**RES 0603 1K %5 1/10W")
      (footprint "eagle-import:R0603_ENKO")
      (libsource (lib "eagle-import") (part "R-EU_R0603E"))
    )
    (comp (ref "R122")
      (value "1200970518**RES 0603 10K %5 1/10W")
      (footprint "eagle-import:R0603_ENKO")
      (libsource (lib "eagle-import") (part "R-EU_R0603E"))
    )
    (comp (ref "R123")
      (value "1200970522**RES 0603 1K %5 1/10W")
      (footprint "eagle-import:R0603_ENKO")
      (libsource (lib "eagle-import") (part "R-EU_R0603E"))
    )
    (comp (ref "R124")
      (value "1200970522**RES 0603 1K %5 1/10W")
      (footprint "eagle-import:R0603_ENKO")
      (libsource (lib "eagle-import") (part "R-EU_R0603E"))
    )
    (comp (ref "R128")
      (value "1200970515**RES 0603 100K %5 1/10W")
      (footprint "eagle-import:R0603_ENKO")
      (libsource (lib "eagle-import") (part "R-EU_R0603E"))
    )
    (comp (ref "R132")
      (value "1200970522**RES 0603 1K %5 1/10W")
      (footprint "eagle-import:R0603_ENKO")
      (libsource (lib "eagle-import") (part "R-EU_R0603E"))
    )
    (comp (ref "R135")
      (value "1200970516**RES 0603 22K %5 1/10W")
      (footprint "eagle-import:R0603_ENKO")
      (libsource (lib "eagle-import") (part "R-EU_R0603E"))
    )
    (comp (ref "R139")
      (value "NC**TAKILMAYACAK")
      (footprint "eagle-import:R0603_ENKO")
      (libsource (lib "eagle-import") (part "R-EU_R0603E"))
    )
    (comp (ref "R140")
      (value "1200970522**RES 0603 1K %5 1/10W")
      (footprint "eagle-import:R0603_ENKO")
      (libsource (lib "eagle-import") (part "R-EU_R0603E"))
    )
    (comp (ref "R141")
      (value "1200970522**RES 0603 1K %5 1/10W")
      (footprint "eagle-import:R0603_ENKO")
      (libsource (lib "eagle-import") (part "R-EU_R0603E"))
    )
    (comp (ref "R142")
      (value "1200970518**RES 0603 10K %5 1/10W")
      (footprint "eagle-import:R0603_ENKO")
      (libsource (lib "eagle-import") (part "R-EU_R0603E"))
    )
    (comp (ref "R144")
      (value "1029-2337**RES 0603 39K %1")
      (footprint "eagle-import:R0603_ENKO")
      (libsource (lib "eagle-import") (part "R-EU_R0603E"))
    )
    (comp (ref "R146")
      (value "1200970585**RES 0603 1M %5 1/10W")
      (footprint "eagle-import:R0603_ENKO")
      (libsource (lib "eagle-import") (part "R-EU_R0603E"))
    )
    (comp (ref "R148")
      (value "1029-6015**RES 1206 56K %5")
      (footprint "eagle-import:R1206_ENKO")
      (libsource (lib "eagle-import") (part "R-EU_R1206E"))
    )
    (comp (ref "T1")
      (value "1109-1016**Transistor NPN 3A 100V 15W Hfemin:10 DPAK Diodes MJD31C-13")
      (footprint "eagle-import:DPAK")
      (libsource (lib "eagle-import") (part "MJD31"))
    )
    (comp (ref "T2")
      (value "1109-4205**Mosfet N-Ch 220mA 50V Rds:1.16R SOT-23 INFINEON BSS138")
      (footprint "eagle-import:SOT-23")
      (libsource (lib "eagle-import") (part "NMOSSOT23"))
    )
    (comp (ref "T3")
      (value "1200980091**TRANS SMD PNP BC857B SOT-23")
      (footprint "eagle-import:SOT23-BEC")
      (libsource (lib "eagle-import") (part "-PNP-SOT23-BECBC856B"))
    )
    (comp (ref "T5")
      (value "1200980539**TRANS SM PNP NSS1C200LT1G SOT-23 100V 3A")
      (footprint "eagle-import:SOT23-BEC")
      (libsource (lib "eagle-import") (part "-PNP-SOT23-BECBC856B"))
    )
    (comp (ref "TRF1")
      (value "0319-7470**SMPS TRAFO 300W LLC E42/21/15 300uH DBC2 [ARGE?]-DENEME")
      (footprint "eagle-import:DEIF_TRF_300W_2")
      (libsource (lib "eagle-import") (part "DEIF_TRF_300W_2"))
    )
    (comp (ref "U1")
      (value "1039-2420**PFC Controller CCM Mode Texas Instruments UCC28019A")
      (footprint "eagle-import:UCC28180")
      (libsource (lib "eagle-import") (part "UCC28180"))
    )
    (comp (ref "U2")
      (value "0319-7472**INDUCTOR 300W LLC-2 TOROID DBC2 [ARGE?]-DENEME")
      (footprint "eagle-import:IND_TOROID")
      (libsource (lib "eagle-import") (part "IND_TOROID"))
    )
    (comp (ref "U3")
      (value "1039-2421**LLC Controller Texas Instruments UCC256301")
      (footprint "eagle-import:SOIC16_UCC256301")
      (libsource (lib "eagle-import") (part "UCC256301"))
    )
    (comp (ref "U4")
      (value "0319-7471**INDUCTOR 300W LLC TOROID DBC2 [ARGE?]-DENEME")
      (footprint "eagle-import:IND_TOROID")
      (libsource (lib "eagle-import") (part "IND_TOROID"))
    )
    (comp (ref "VR1")
      (value "0169-3008**Varistor 20mm 360VAC 470VDC (AbC)")
      (footprint "eagle-import:VITRA_VARISTOR")
      (libsource (lib "eagle-import") (part "VITRA_VARISTOR"))
    )
    (comp (ref "X1")
      (value "0289-1462**GMSTBA 2.5/ 3-G-7.62 (Phoenix 1766246)")
      (footprint "eagle-import:GMSTBA3")
      (fields (field (name "MF") "FARNELL") (field (name "MPN") "1757255"))
      (libsource (lib "eagle-import") (part "GMSTBA3"))
    )
    (comp (ref "X1-K")
      (value "0289-1463**GMVSTBR 2.5/ 3-ST-7.62 (Phoenix 1832536)")
      (footprint "eagle-import:SOKET")
      (libsource (lib "eagle-import") (part "SOKET"))
    )
    (comp (ref "X2-K")
      (value "0289-1461**MVSTBR 2.5/ 4-ST-5.08 (Phoenix 1792265)")
      (footprint "eagle-import:SOKET")
      (libsource (lib "eagle-import") (part "SOKET"))
    )
    (comp (ref "X4")
      (value "0289-1460**MSTBA 2.5/ 4-G-5.08 (Phoenix 1757268)")
      (footprint "eagle-import:MSTBA4")
      (fields (field (name "MF") "FARNELL") (field (name "MPN") "1757268"))
      (libsource (lib "eagle-import") (part "MSTBA4"))
    )
    (comp (ref "Z1")
      (value "1129-1145**ZENER SOT23 0.3W 15V BZX84C15")
      (footprint "eagle-import:SOT23")
      (libsource (lib "eagle-import") (part "ZENER-DIODESOT23"))
    )
    (comp (ref "Z2")
      (value "1129-1152**ZENER SOT23 10V 0.4W BZX84-C10")
      (footprint "eagle-import:SOT23")
      (libsource (lib "eagle-import") (part "ZENER-DIODESOT23"))
    )
    (comp (ref "Z3")
      (value "1129-1150**ZENER SOT23 6V2 225mW BZX84C6V2 (AbC)")
      (footprint "eagle-import:SOT23")
      (libsource (lib "eagle-import") (part "ZENER-DIODESOT23"))
    )
    (comp (ref "Z5")
      (value "1129-1163**ZENER SOT23 20V 400mW %5 BZX84C20V")
      (footprint "eagle-import:SOT23")
      (libsource (lib "eagle-import") (part "ZENER-DIODESOT23"))
    )
    (comp (ref "Z6")
      (value "1129-1152**ZENER SOT23 10V 0.4W BZX84-C10")
      (footprint "eagle-import:SOT23")
      (libsource (lib "eagle-import") (part "ZENER-DIODESOT23"))
    )
    (comp (ref "Z8")
      (value "NC**TAKILMAYACAK")
      (footprint "eagle-import:SOT23")
      (libsource (lib "eagle-import") (part "ZENER-DIODESOT23"))
    )
    (comp (ref "Z9")
      (value "1129-1150**ZENER SOT23 6V2 225mW BZX84C6V2 (AbC)")
      (footprint "eagle-import:SOT23")
      (libsource (lib "eagle-import") (part "ZENER-DIODESOT23"))
    )
  )
  (nets
    (net (code "1") (name "+3V3") (class "Default")
      (node (ref "C79") (pin "1") (pinfunction "1_1") (pintype "passive"))
      (node (ref "IC5") (pin "8") (pinfunction "V+_8") (pintype "power_in"))
      (node (ref "JP5") (pin "9") (pinfunction "9_9") (pintype "passive"))
      (node (ref "R135") (pin "2") (pinfunction "2_2") (pintype "passive"))
    )
    (net (code "2") (name "+12V") (class "Default")
      (node (ref "C49") (pin "2") (pinfunction "2_2") (pintype "passive"))
      (node (ref "C50") (pin "2") (pinfunction "2_2") (pintype "passive"))
      (node (ref "C55") (pin "2") (pinfunction "2_2") (pintype "passive"))
      (node (ref "C56") (pin "2") (pinfunction "2_2") (pintype "passive"))
      (node (ref "C72") (pin "1") (pinfunction "1_1") (pintype "passive"))
      (node (ref "C73") (pin "1") (pinfunction "1_1") (pintype "passive"))
      (node (ref "C74") (pin "1") (pinfunction "1_1") (pintype "passive"))
      (node (ref "C75") (pin "1") (pinfunction "1_1") (pintype "passive"))
      (node (ref "C98") (pin "2") (pinfunction "2_2") (pintype "passive"))
      (node (ref "IC2") (pin "1") (pinfunction "1.VCC_1") (pintype "power_in"))
      (node (ref "IC3") (pin "1") (pinfunction "1.VCC_1") (pintype "power_in"))
      (node (ref "JP5") (pin "5") (pinfunction "5_5") (pintype "passive"))
      (node (ref "OC1") (pin "1") (pinfunction "1_1") (pintype "passive"))
      (node (ref "R102") (pin "1") (pinfunction "1_1") (pintype "passive"))
      (node (ref "R128") (pin "2") (pinfunction "2_2") (pintype "passive"))
    )
    (net (code "3") (name "/30V") (class "Default")
      (node (ref "C108") (pin "2") (pinfunction "2_2") (pintype "passive"))
      (node (ref "C110") (pin "1") (pinfunction "1_1") (pintype "passive"))
      (node (ref "C111") (pin "1") (pinfunction "1_1") (pintype "passive"))
      (node (ref "C58") (pin "1") (pinfunction "1_1") (pintype "passive"))
      (node (ref "C58") (pin "3") (pinfunction "1_3") (pintype "passive"))
      (node (ref "C59") (pin "1") (pinfunction "1_1") (pintype "passive"))
      (node (ref "C61") (pin "+") (pinfunction "+_+") (pintype "passive"))
      (node (ref "C61") (pin "+1") (pinfunction "+_+1") (pintype "passive"))
      (node (ref "C62") (pin "+") (pinfunction "+_+") (pintype "passive"))
      (node (ref "C62") (pin "+1") (pinfunction "+_+1") (pintype "passive"))
      (node (ref "C64") (pin "+") (pinfunction "+_+") (pintype "passive"))
      (node (ref "C64") (pin "+1") (pinfunction "+_+1") (pintype "passive"))
      (node (ref "C65") (pin "+") (pinfunction "+_+") (pintype "passive"))
      (node (ref "C65") (pin "+1") (pinfunction "+_+1") (pintype "passive"))
      (node (ref "JP5") (pin "7") (pinfunction "7_7") (pintype "passive"))
      (node (ref "OC2") (pin "1") (pinfunction "1_1") (pintype "passive"))
      (node (ref "R112") (pin "2") (pinfunction "2_2") (pintype "passive"))
      (node (ref "R148") (pin "1") (pinfunction "1_1") (pintype "passive"))
      (node (ref "TRF1") (pin "11") (pinfunction "14_11") (pintype "passive"))
      (node (ref "TRF1") (pin "12") (pinfunction "15_12") (pintype "passive"))
      (node (ref "TRF1") (pin "13") (pinfunction "16_13") (pintype "passive"))
      (node (ref "TRF1") (pin "19") (pinfunction "15_19") (pintype "passive"))
      (node (ref "TRF1") (pin "20") (pinfunction "14_20") (pintype "passive"))
      (node (ref "TRF1") (pin "24") (pinfunction "10_24") (pintype "passive"))
      (node (ref "TRF1") (pin "25") (pinfunction "16_25") (pintype "passive"))
      (node (ref "TRF1") (pin "27") (pinfunction "10_27") (pintype "passive"))
      (node (ref "TRF1") (pin "31") (pinfunction "14_31") (pintype "passive"))
      (node (ref "TRF1") (pin "32") (pinfunction "15_32") (pintype "passive"))
      (node (ref "TRF1") (pin "38") (pinfunction "16_38") (pintype "passive"))
      (node (ref "TRF1") (pin "40") (pinfunction "9_40") (pintype "passive"))
      (node (ref "TRF1") (pin "41") (pinfunction "10_41") (pintype "passive"))
      (node (ref "TRF1") (pin "45") (pinfunction "14_45") (pintype "passive"))
      (node (ref "TRF1") (pin "46") (pinfunction "15_46") (pintype "passive"))
      (node (ref "TRF1") (pin "47") (pinfunction "16_47") (pintype "passive"))
      (node (ref "TRF1") (pin "6.1") (pinfunction "9_6.1") (pintype "passive"))
      (node (ref "TRF1") (pin "6.2") (pinfunction "9_6.2") (pintype "passive"))
      (node (ref "TRF1") (pin "6.5") (pinfunction "9_6.5") (pintype "passive"))
      (node (ref "TRF1") (pin "7") (pinfunction "10_7") (pintype "passive"))
      (node (ref "X4") (pin "3") (pinfunction "1_3") (pintype "passive"))
      (node (ref "X4") (pin "4") (pinfunction "1_4") (pintype "passive"))
    )
    (net (code "4") (name "/I_FOR_REV_BAT_PROTEC") (class "Default")
      (node (ref "C84") (pin "2") (pinfunction "2_2") (pintype "passive"))
      (node (ref "IC5") (pin "3") (pinfunction "+IN_3") (pintype "input"))
      (node (ref "IC5") (pin "7") (pinfunction "OUT_7") (pintype "output"))
      (node (ref "R104") (pin "2") (pinfunction "2_2") (pintype "passive"))
      (node (ref "R132") (pin "2") (pinfunction "2_2") (pintype "passive"))
    )
    (net (code "5") (name "/RES") (class "Default")
      (node (ref "C43") (pin "2") (pinfunction "2_2") (pintype "passive"))
      (node (ref "C54") (pin "2") (pinfunction "2_2") (pintype "passive"))
      (node (ref "IC2") (pin "4") (pinfunction "4.LLD_4") (pintype "input"))
      (node (ref "IC3") (pin "4") (pinfunction "4.LLD_4") (pintype "input"))
      (node (ref "R62") (pin "1") (pinfunction "1_1") (pintype "passive"))
      (node (ref "R80") (pin "1") (pinfunction "1_1") (pintype "passive"))
    )
    (net (code "6") (name "/VOUT") (class "Default")
      (node (ref "C22") (pin "1") (pinfunction "1_1") (pintype "passive"))
      (node (ref "C31") (pin "1") (pinfunction "1_1") (pintype "passive"))
      (node (ref "C38") (pin "+") (pinfunction "+_+") (pintype "passive"))
      (node (ref "D3") (pin "C") (pinfunction "C_C") (pintype "passive"))
      (node (ref "D5") (pin "K") (pinfunction "C_K") (pintype "passive"))
      (node (ref "Q3") (pin "2") (pinfunction "D_2") (pintype "passive"))
      (node (ref "R27") (pin "1") (pinfunction "1_1") (pintype "passive"))
      (node (ref "R28") (pin "1") (pinfunction "1_1") (pintype "passive"))
      (node (ref "R29") (pin "1") (pinfunction "1_1") (pintype "passive"))
      (node (ref "R33") (pin "2") (pinfunction "2_2") (pintype "passive"))
      (node (ref "R38") (pin "2") (pinfunction "2_2") (pintype "passive"))
    )
    (net (code "7") (name "/VREF2.1") (class "Default")
      (node (ref "IC4") (pin "1") (pinfunction "VREF_1") (pintype "bidirectional"))
      (node (ref "IC4") (pin "5") (pinfunction "CV+_5") (pintype "input"))
      (node (ref "R92") (pin "1") (pinfunction "1_1") (pintype "passive"))
    )
    (net (code "8") (name "BLK") (class "Default")
      (node (ref "C29") (pin "2") (pinfunction "2_2") (pintype "passive"))
      (node (ref "R41") (pin "1") (pinfunction "1_1") (pintype "passive"))
      (node (ref "R42") (pin "2") (pinfunction "2_2") (pintype "passive"))
      (node (ref "U3") (pin "4") (pinfunction "BLK_4") (pintype "bidirectional"))
    )
    (net (code "9") (name "BW") (class "Default")
      (node (ref "R2") (pin "2") (pinfunction "2_2") (pintype "passive"))
      (node (ref "R3") (pin "2") (pinfunction "2_2") (pintype "passive"))
      (node (ref "U3") (pin "8") (pinfunction "BW_8") (pintype "input"))
    )
    (net (code "10") (name "CUT_OFF_OUTPUT") (class "Default")
      (node (ref "C103") (pin "1") (pinfunction "1_1") (pintype "passive"))
      (node (ref "D18") (pin "A") (pinfunction "A_A") (pintype "passive"))
      (node (ref "JP5") (pin "6") (pinfunction "6_6") (pintype "passive"))
      (node (ref "R135") (pin "1") (pinfunction "1_1") (pintype "passive"))
    )
    (net (code "11") (name "GND") (class "Default")
      (node (ref "C10") (pin "1") (pinfunction "1_1") (pintype "passive"))
      (node (ref "C11") (pin "1") (pinfunction "1_1") (pintype "passive"))
      (node (ref "C12") (pin "2") (pinfunction "2_2") (pintype "passive"))
      (node (ref "C13") (pin "2") (pinfunction "2_2") (pintype "passive"))
      (node (ref "C14") (pin "2") (pinfunction "2_2") (pintype "passive"))
      (node (ref "C15") (pin "2") (pinfunction "2_2") (pintype "passive"))
      (node (ref "C16") (pin "2") (pinfunction "2_2") (pintype "passive"))
      (node (ref "C17") (pin "2") (pinfunction "2_2") (pintype "passive"))
      (node (ref "C18") (pin "2") (pinfunction "2_2") (pintype "passive"))
      (node (ref "C19") (pin "2") (pinfunction "2_2") (pintype "passive"))
      (node (ref "C21") (pin "1") (pinfunction "1_1") (pintype "passive"))
      (node (ref "C22") (pin "2") (pinfunction "2_2") (pintype "passive"))
      (node (ref "C23") (pin "2") (pinfunction "2_2") (pintype "passive"))
      (node (ref "C24") (pin "P$1") (pinfunction "1_P$1") (pintype "passive"))
      (node (ref "C25") (pin "2") (pinfunction "2_2") (pintype "passive"))
      (node (ref "C26") (pin "-") (pinfunction "-_-") (pintype "passive"))
      (node (ref "C27") (pin "2") (pinfunction "2_2") (pintype "passive"))
      (node (ref "C28") (pin "2") (pinfunction "2_2") (pintype "passive"))
      (node (ref "C29") (pin "1") (pinfunction "1_1") (pintype "passive"))
      (node (ref "C30") (pin "2") (pinfunction "2_2") (pintype "passive"))
      (node (ref "C31") (pin "2") (pinfunction "2_2") (pintype "passive"))
      (node (ref "C32") (pin "2") (pinfunction "2_2") (pintype "passive"))
      (node (ref "C33") (pin "2") (pinfunction "2_2") (pintype "passive"))
      (node (ref "C38") (pin "-") (pinfunction "-_-") (pintype "passive"))
      (node (ref "C7") (pin "1") (pinfunction "1_1") (pintype "passive"))
      (node (ref "C9") (pin "1") (pinfunction "1_1") (pintype "passive"))
      (node (ref "OC1") (pin "3") (pinfunction "3_3") (pintype "passive"))
      (node (ref "OC2") (pin "3") (pinfunction "3_3") (pintype "passive"))
      (node (ref "Q1") (pin "2") (pinfunction "E_2") (pintype "passive"))
      (node (ref "Q2") (pin "S") (pinfunction "S_S") (pintype "passive"))
      (node (ref "Q4") (pin "3") (pinfunction "S_3") (pintype "passive"))
      (node (ref "R10") (pin "1") (pinfunction "1_1") (pintype "passive"))
      (node (ref "R14") (pin "1") (pinfunction "1_1") (pintype "passive"))
      (node (ref "R16") (pin "1") (pinfunction "1_1") (pintype "passive"))
      (node (ref "R19") (pin "2") (pinfunction "2_2") (pintype "passive"))
      (node (ref "R20") (pin "2") (pinfunction "2_2") (pintype "passive"))
      (node (ref "R22") (pin "2") (pinfunction "2_2") (pintype "passive"))
      (node (ref "R3") (pin "1") (pinfunction "1_1") (pintype "passive"))
      (node (ref "R31") (pin "2") (pinfunction "2_2") (pintype "passive"))
      (node (ref "R43") (pin "1") (pinfunction "1_1") (pintype "passive"))
      (node (ref "R49") (pin "2") (pinfunction "2_2") (pintype "passive"))
      (node (ref "R51") (pin "1") (pinfunction "1_1") (pintype "passive"))
      (node (ref "R7") (pin "1") (pinfunction "1_1") (pintype "passive"))
      (node (ref "T2") (pin "2") (pinfunction "S_2") (pintype "passive"))
      (node (ref "TRF1") (pin "14") (pinfunction "7_14") (pintype "passive"))
      (node (ref "TRF1") (pin "26") (pinfunction "8_26") (pintype "passive"))
      (node (ref "TRF1") (pin "33") (pinfunction "7_33") (pintype "passive"))
      (node (ref "TRF1") (pin "39") (pinfunction "8_39") (pintype "passive"))
      (node (ref "TRF1") (pin "4") (pinfunction "8_4") (pintype "passive"))
      (node (ref "TRF1") (pin "48") (pinfunction "8_48") (pintype "passive"))
      (node (ref "TRF1") (pin "49") (pinfunction "7_49") (pintype "passive"))
      (node (ref "TRF1") (pin "6") (pinfunction "7_6") (pintype "passive"))
      (node (ref "U1") (pin "1") (pinfunction "GND_1") (pintype "bidirectional"))
      (node (ref "U3") (pin "11") (pinfunction "GND_11") (pintype "power_in"))
      (node (ref "Z1") (pin "1") (pinfunction "A_1") (pintype "passive"))
    )
    (net (code "12") (name "GNDA") (class "Default")
      (node (ref "C103") (pin "2") (pinfunction "2_2") (pintype "passive"))
      (node (ref "C108") (pin "1") (pinfunction "1_1") (pintype "passive"))
      (node (ref "C72") (pin "2") (pinfunction "2_2") (pintype "passive"))
      (node (ref "C73") (pin "2") (pinfunction "2_2") (pintype "passive"))
      (node (ref "C74") (pin "2") (pinfunction "2_2") (pintype "passive"))
      (node (ref "C75") (pin "2") (pinfunction "2_2") (pintype "passive"))
      (node (ref "C78") (pin "1") (pinfunction "1_1") (pintype "passive"))
      (node (ref "C80") (pin "1") (pinfunction "1_1") (pintype "passive"))
      (node (ref "C90") (pin "2") (pinfunction "2_2") (pintype "passive"))
      (node (ref "C91") (pin "1") (pinfunction "1_1") (pintype "passive"))
      (node (ref "C92") (pin "1") (pinfunction "1_1") (pintype "passive"))
      (node (ref "C95") (pin "1") (pinfunction "1_1") (pintype "passive"))
      (node (ref "C98") (pin "1") (pinfunction "1_1") (pintype "passive"))
      (node (ref "IC4") (pin "6") (pinfunction "GND_6") (pintype "power_in"))
      (node (ref "IC8") (pin "S") (pinfunction "S123_S") (pintype "passive"))
      (node (ref "IC8") (pin "S1") (pinfunction "S123_S1") (pintype "passive"))
      (node (ref "IC8") (pin "S2") (pinfunction "S123_S2") (pintype "passive"))
      (node (ref "JP5") (pin "1") (pinfunction "1_1") (pintype "passive"))
      (node (ref "JP5") (pin "3") (pinfunction "3_3") (pintype "passive"))
      (node (ref "Q11") (pin "2") (pinfunction "E_2") (pintype "passive"))
      (node (ref "Q13") (pin "2") (pinfunction "E_2") (pintype "passive"))
      (node (ref "Q14") (pin "2") (pinfunction "E_2") (pintype "passive"))
      (node (ref "R100") (pin "2") (pinfunction "2_2") (pintype "passive"))
      (node (ref "R115") (pin "1") (pinfunction "1_1") (pintype "passive"))
      (node (ref "R116") (pin "1") (pinfunction "1_1") (pintype "passive"))
      (node (ref "R117") (pin "2") (pinfunction "2_2") (pintype "passive"))
      (node (ref "R122") (pin "1") (pinfunction "1_1") (pintype "passive"))
      (node (ref "R139") (pin "1") (pinfunction "1_1") (pintype "passive"))
      (node (ref "R142") (pin "2") (pinfunction "2_2") (pintype "passive"))
      (node (ref "R146") (pin "1") (pinfunction "1_1") (pintype "passive"))
      (node (ref "R97") (pin "2") (pinfunction "2_2") (pintype "passive"))
      (node (ref "R98") (pin "2") (pinfunction "2_2") (pintype "passive"))
      (node (ref "R99") (pin "2") (pinfunction "2_2") (pintype "passive"))
      (node (ref "Z6") (pin "1") (pinfunction "A_1") (pintype "passive"))
    )
    (net (code "13") (name "GNDIO") (class "Default")
      (node (ref "C112") (pin "2") (pinfunction "2_2") (pintype "passive"))
      (node (ref "D20") (pin "C") (pinfunction "C_C") (pintype "passive"))
      (node (ref "IC8") (pin "D") (pinfunction "D5678_D") (pintype "passive"))
      (node (ref "IC8") (pin "D1") (pinfunction "D5678_D1") (pintype "passive"))
      (node (ref "IC8") (pin "D2") (pinfunction "D5678_D2") (pintype "passive"))
      (node (ref "IC8") (pin "D3") (pinfunction "D5678_D3") (pintype "passive"))
      (node (ref "IC8") (pin "P$1") (pinfunction "D5678_P$1") (pintype "passive"))
      (node (ref "IC8") (pin "P$2") (pinfunction "D5678_P$2") (pintype "passive"))
      (node (ref "JP5") (pin "11") (pinfunction "11_11") (pintype "passive"))
      (node (ref "T5") (pin "E") (pinfunction "E_E") (pintype "passive"))
      (node (ref "X4") (pin "1") (pinfunction "1_1") (pintype "passive"))
      (node (ref "X4") (pin "2") (pinfunction "1_2") (pintype "passive"))
    )
    (net (code "14") (name "HO") (class "Default")
      (node (ref "D9") (pin "A") (pinfunction "A_A") (pintype "passive"))
      (node (ref "Q3") (pin "1") (pinfunction "G_1") (pintype "passive"))
      (node (ref "R47") (pin "2") (pinfunction "2_2") (pintype "passive"))
    )
    (net (code "15") (name "HS") (class "Default")
      (node (ref "C35") (pin "1") (pinfunction "1_1") (pintype "passive"))
      (node (ref "Q3") (pin "3") (pinfunction "S_3") (pintype "passive"))
      (node (ref "Q4") (pin "2") (pinfunction "D_2") (pintype "passive"))
      (node (ref "U3") (pin "16") (pinfunction "HS_16") (pintype "bidirectional"))
      (node (ref "U4") (pin "1") (pinfunction "P1_1") (pintype "passive"))
    )
    (net (code "16") (name "ISNS") (class "Default")
      (node (ref "C25") (pin "1") (pinfunction "1_1") (pintype "passive"))
      (node (ref "C34") (pin "2") (pinfunction "2_2") (pintype "passive"))
      (node (ref "R31") (pin "1") (pinfunction "1_1") (pintype "passive"))
      (node (ref "U3") (pin "6") (pinfunction "ISNS_6") (pintype "input"))
    )
    (net (code "17") (name "I_OUT_ADC") (class "Default")
      (node (ref "C92") (pin "2") (pinfunction "2_2") (pintype "passive"))
      (node (ref "JP5") (pin "10") (pinfunction "10_10") (pintype "passive"))
      (node (ref "R118") (pin "2") (pinfunction "2_2") (pintype "passive"))
    )
    (net (code "18") (name "I_PWM") (class "Default")
      (node (ref "JP5") (pin "4") (pinfunction "4_4") (pintype "passive"))
      (node (ref "R89") (pin "2") (pinfunction "2_2") (pintype "passive"))
    )
    (net (code "19") (name "LLC_VAC_IN1") (class "Default")
      (node (ref "B1") (pin "AC1") (pinfunction "AC1_AC1") (pintype "passive"))
      (node (ref "C4") (pin "1") (pinfunction "1_1") (pintype "passive"))
      (node (ref "C5") (pin "1") (pinfunction "1_1") (pintype "passive"))
      (node (ref "D6") (pin "A") (pinfunction "A_A") (pintype "passive"))
      (node (ref "L1") (pin "3") (pinfunction "3_3") (pintype "passive"))
    )
    (net (code "20") (name "LLC_VAC_IN2") (class "Default")
      (node (ref "B1") (pin "AC2") (pinfunction "AC2_AC2") (pintype "passive"))
      (node (ref "C4") (pin "2") (pinfunction "2_2") (pintype "passive"))
      (node (ref "C6") (pin "1") (pinfunction "1_1") (pintype "passive"))
      (node (ref "D7") (pin "A") (pinfunction "A_A") (pintype "passive"))
      (node (ref "L1") (pin "4") (pinfunction "4_4") (pintype "passive"))
    )
    (net (code "21") (name "LO") (class "Default")
      (node (ref "D8") (pin "A") (pinfunction "A_A") (pintype "passive"))
      (node (ref "Q4") (pin "1") (pinfunction "G_1") (pintype "passive"))
      (node (ref "R46") (pin "2") (pinfunction "2_2") (pintype "passive"))
    )
    (net (code "22") (name "Net-(B1-Pad-)") (class "Default")
      (node (ref "B1") (pin "-") (pinfunction "-_-") (pintype "passive"))
      (node (ref "C8") (pin "2") (pinfunction "2_2") (pintype "passive"))
      (node (ref "R12") (pin "1") (pinfunction "1_1") (pintype "passive"))
      (node (ref "R17") (pin "1") (pinfunction "1_1") (pintype "passive"))
      (node (ref "R18") (pin "1") (pinfunction "1_1") (pintype "passive"))
    )
    (net (code "23") (name "Net-(C2-Pad1)") (class "Default")
      (node (ref "C2") (pin "1") (pinfunction "1_1") (pintype "passive"))
      (node (ref "C3") (pin "2") (pinfunction "2_2") (pintype "passive"))
      (node (ref "F1") (pin "2") (pinfunction "2_2") (pintype "passive"))
      (node (ref "L1") (pin "1") (pinfunction "1_1") (pintype "passive"))
      (node (ref "VR1") (pin "2") (pinfunction "2_2") (pintype "passive"))
    )
    (net (code "24") (name "Net-(C16-Pad1)") (class "Default")
      (node (ref "C16") (pin "1") (pinfunction "1_1") (pintype "passive"))
      (node (ref "R15") (pin "1") (pinfunction "1_1") (pintype "passive"))
    )
    (net (code "25") (name "Net-(C20-Pad2)") (class "Default")
      (node (ref "C20") (pin "2") (pinfunction "2_2") (pintype "passive"))
      (node (ref "R27") (pin "2") (pinfunction "2_2") (pintype "passive"))
      (node (ref "R28") (pin "2") (pinfunction "2_2") (pintype "passive"))
      (node (ref "R29") (pin "2") (pinfunction "2_2") (pintype "passive"))
    )
    (net (code "26") (name "Net-(C21-Pad2)") (class "Default")
      (node (ref "C21") (pin "2") (pinfunction "2_2") (pintype "passive"))
      (node (ref "R23") (pin "2") (pinfunction "2_2") (pintype "passive"))
      (node (ref "R25") (pin "2") (pinfunction "2_2") (pintype "passive"))
      (node (ref "R26") (pin "2") (pinfunction "2_2") (pintype "passive"))
      (node (ref "R30") (pin "2") (pinfunction "2_2") (pintype "passive"))
    )
    (net (code "27") (name "Net-(C24-2)") (class "Default")
      (node (ref "C24") (pin "P$2") (pinfunction "2_P$2") (pintype "passive"))
      (node (ref "C43") (pin "1") (pinfunction "1_1") (pintype "passive"))
      (node (ref "C49") (pin "1") (pinfunction "1_1") (pintype "passive"))
      (node (ref "C50") (pin "1") (pinfunction "1_1") (pintype "passive"))
      (node (ref "C53") (pin "1") (pinfunction "1_1") (pintype "passive"))
      (node (ref "C54") (pin "1") (pinfunction "1_1") (pintype "passive"))
      (node (ref "C55") (pin "1") (pinfunction "1_1") (pintype "passive"))
      (node (ref "C56") (pin "1") (pinfunction "1_1") (pintype "passive"))
      (node (ref "C59") (pin "2") (pinfunction "2_2") (pintype "passive"))
      (node (ref "C61") (pin "-") (pinfunction "-_-") (pintype "passive"))
      (node (ref "C61") (pin "-1") (pinfunction "-_-1") (pintype "passive"))
      (node (ref "C62") (pin "-") (pinfunction "-_-") (pintype "passive"))
      (node (ref "C62") (pin "-1") (pinfunction "-_-1") (pintype "passive"))
      (node (ref "C64") (pin "-") (pinfunction "-_-") (pintype "passive"))
      (node (ref "C64") (pin "-1") (pinfunction "-_-1") (pintype "passive"))
      (node (ref "C65") (pin "-") (pinfunction "-_-") (pintype "passive"))
      (node (ref "C65") (pin "-1") (pinfunction "-_-1") (pintype "passive"))
      (node (ref "C79") (pin "2") (pinfunction "2_2") (pintype "passive"))
      (node (ref "D11") (pin "A") (pinfunction "A_A") (pintype "passive"))
      (node (ref "D13") (pin "A") (pinfunction "A_A") (pintype "passive"))
      (node (ref "IC2") (pin "5") (pinfunction "5.TRIG_5") (pintype "output"))
      (node (ref "IC2") (pin "7") (pinfunction "7.GND_7") (pintype "input"))
      (node (ref "IC3") (pin "5") (pinfunction "5.TRIG_5") (pintype "output"))
      (node (ref "IC3") (pin "7") (pinfunction "7.GND_7") (pintype "input"))
      (node (ref "IC5") (pin "4") (pinfunction "V-_4") (pintype "power_in"))
      (node (ref "Q12") (pin "2") (pinfunction "E_2") (pintype "passive"))
      (node (ref "Q5") (pin "S") (pinfunction "S_S") (pintype "passive"))
      (node (ref "Q7") (pin "S") (pinfunction "S_S") (pintype "passive"))
      (node (ref "R101") (pin "1") (pinfunction "1_1") (pintype "passive"))
      (node (ref "R108") (pin "1") (pinfunction "1_1") (pintype "passive"))
      (node (ref "R51") (pin "2") (pinfunction "2_2") (pintype "passive"))
      (node (ref "R54") (pin "2") (pinfunction "2_2") (pintype "passive"))
      (node (ref "R55") (pin "2") (pinfunction "2_2") (pintype "passive"))
      (node (ref "R56") (pin "2") (pinfunction "2_2") (pintype "passive"))
      (node (ref "R61") (pin "2") (pinfunction "2_2") (pintype "passive"))
      (node (ref "R62") (pin "2") (pinfunction "2_2") (pintype "passive"))
      (node (ref "R63") (pin "2") (pinfunction "2_2") (pintype "passive"))
      (node (ref "R64") (pin "2") (pinfunction "2_2") (pintype "passive"))
      (node (ref "R68") (pin "2") (pinfunction "2_2") (pintype "passive"))
      (node (ref "R69") (pin "2") (pinfunction "2_2") (pintype "passive"))
      (node (ref "R70") (pin "2") (pinfunction "2_2") (pintype "passive"))
      (node (ref "R78") (pin "2") (pinfunction "2_2") (pintype "passive"))
      (node (ref "R80") (pin "2") (pinfunction "2_2") (pintype "passive"))
      (node (ref "R81") (pin "2") (pinfunction "2_2") (pintype "passive"))
      (node (ref "R82") (pin "2") (pinfunction "2_2") (pintype "passive"))
      (node (ref "R96") (pin "1") (pinfunction "1_1") (pintype "passive"))
      (node (ref "R97") (pin "1") (pinfunction "1_1") (pintype "passive"))
      (node (ref "R98") (pin "1") (pinfunction "1_1") (pintype "passive"))
      (node (ref "Z9") (pin "1") (pinfunction "A_1") (pintype "passive"))
    )
    (net (code "28") (name "Net-(C33-Pad1)") (class "Default")
      (node (ref "C33") (pin "1") (pinfunction "1_1") (pintype "passive"))
      (node (ref "C34") (pin "1") (pinfunction "1_1") (pintype "passive"))
      (node (ref "C36") (pin "1") (pinfunction "1_1") (pintype "passive"))
      (node (ref "TRF1") (pin "55") (pinfunction "1_55") (pintype "passive"))
      (node (ref "TRF1") (pin "56") (pinfunction "1_56") (pintype "passive"))
      (node (ref "TRF1") (pin "57") (pinfunction "1_57") (pintype "passive"))
      (node (ref "TRF1") (pin "58") (pinfunction "1_58") (pintype "passive"))
    )
    (net (code "29") (name "Net-(C39-Pad2)") (class "Default")
      (node (ref "C39") (pin "2") (pinfunction "2_2") (pintype "passive"))
      (node (ref "R54") (pin "1") (pinfunction "1_1") (pintype "passive"))
      (node (ref "R55") (pin "1") (pinfunction "1_1") (pintype "passive"))
      (node (ref "R56") (pin "1") (pinfunction "1_1") (pintype "passive"))
    )
    (net (code "30") (name "Net-(C51-Pad2)") (class "Default")
      (node (ref "C51") (pin "2") (pinfunction "2_2") (pintype "passive"))
      (node (ref "R68") (pin "1") (pinfunction "1_1") (pintype "passive"))
      (node (ref "R69") (pin "1") (pinfunction "1_1") (pintype "passive"))
      (node (ref "R70") (pin "1") (pinfunction "1_1") (pintype "passive"))
    )
    (net (code "31") (name "Net-(C78-Pad2)") (class "Default")
      (node (ref "C78") (pin "2") (pinfunction "2_2") (pintype "passive"))
      (node (ref "R91") (pin "2") (pinfunction "2_2") (pintype "passive"))
      (node (ref "R93") (pin "2") (pinfunction "2_2") (pintype "passive"))
    )
    (net (code "32") (name "Net-(C85-Pad1)") (class "Default")
      (node (ref "C85") (pin "1") (pinfunction "1_1") (pintype "passive"))
      (node (ref "R103") (pin "1") (pinfunction "1_1") (pintype "passive"))
    )
    (net (code "33") (name "Net-(C86-Pad1)") (class "Default")
      (node (ref "C86") (pin "1") (pinfunction "1_1") (pintype "passive"))
      (node (ref "R110") (pin "1") (pinfunction "1_1") (pintype "passive"))
    )
    (net (code "34") (name "Net-(C95-Pad2)") (class "Default")
      (node (ref "C95") (pin "2") (pinfunction "2_2") (pintype "passive"))
      (node (ref "R123") (pin "1") (pinfunction "1_1") (pintype "passive"))
      (node (ref "R124") (pin "2") (pinfunction "2_2") (pintype "passive"))
    )
    (net (code "35") (name "Net-(D4-PadA)") (class "Default")
      (node (ref "D4") (pin "A") (pinfunction "A_A") (pintype "passive"))
      (node (ref "Q2") (pin "G") (pinfunction "G_G") (pintype "passive"))
      (node (ref "R21") (pin "1") (pinfunction "1_1") (pintype "passive"))
      (node (ref "R22") (pin "1") (pinfunction "1_1") (pintype "passive"))
    )
    (net (code "36") (name "Net-(D6-PadC)") (class "Default")
      (node (ref "D6") (pin "C") (pinfunction "C_C") (pintype "passive"))
      (node (ref "D7") (pin "C") (pinfunction "C_C") (pintype "passive"))
      (node (ref "R32") (pin "2") (pinfunction "2_2") (pintype "passive"))
    )
    (net (code "37") (name "Net-(D8-PadC)") (class "Default")
      (node (ref "D8") (pin "C") (pinfunction "C_C") (pintype "passive"))
      (node (ref "R44") (pin "2") (pinfunction "2_2") (pintype "passive"))
    )
    (net (code "38") (name "Net-(D9-PadC)") (class "Default")
      (node (ref "D9") (pin "C") (pinfunction "C_C") (pintype "passive"))
      (node (ref "R45") (pin "2") (pinfunction "2_2") (pintype "passive"))
    )
    (net (code "39") (name "Net-(D10-PadA)") (class "Default")
      (node (ref "D10") (pin "A") (pinfunction "A_A") (pintype "passive"))
      (node (ref "R50") (pin "2") (pinfunction "2_2") (pintype "passive"))
    )
    (net (code "40") (name "Net-(D18-PadC)") (class "Default")
      (node (ref "D18") (pin "C") (pinfunction "C_C") (pintype "passive"))
      (node (ref "R140") (pin "2") (pinfunction "2_2") (pintype "passive"))
      (node (ref "R141") (pin "2") (pinfunction "2_2") (pintype "passive"))
    )
    (net (code "41") (name "Net-(D20-PadA)") (class "Default")
      (node (ref "D20") (pin "A") (pinfunction "A_A") (pintype "passive"))
      (node (ref "R148") (pin "2") (pinfunction "2_2") (pintype "passive"))
      (node (ref "T5") (pin "B") (pinfunction "B_B") (pintype "passive"))
    )
    (net (code "42") (name "Net-(IC2-2.MIN_TOFF)") (class "Default")
      (node (ref "IC2") (pin "2") (pinfunction "2.MIN_TOFF_2") (pintype "input"))
      (node (ref "R64") (pin "1") (pinfunction "1_1") (pintype "passive"))
    )
    (net (code "43") (name "Net-(IC2-3.MIN_TON)") (class "Default")
      (node (ref "IC2") (pin "3") (pinfunction "3.MIN_TON_3") (pintype "input"))
      (node (ref "R63") (pin "1") (pinfunction "1_1") (pintype "passive"))
    )
    (net (code "44") (name "Net-(IC2-6.CS)") (class "Default")
      (node (ref "C39") (pin "1") (pinfunction "1_1") (pintype "passive"))
      (node (ref "D11") (pin "C") (pinfunction "C_C") (pintype "passive"))
      (node (ref "IC2") (pin "6") (pinfunction "6.CS_6") (pintype "input"))
      (node (ref "Q5") (pin "D") (pinfunction "D_D") (pintype "passive"))
      (node (ref "TRF1") (pin "23") (pinfunction "11_23") (pintype "passive"))
      (node (ref "TRF1") (pin "28") (pinfunction "11_28") (pintype "passive"))
      (node (ref "TRF1") (pin "42") (pinfunction "11_42") (pintype "passive"))
      (node (ref "TRF1") (pin "8") (pinfunction "11_8") (pintype "passive"))
    )
    (net (code "45") (name "Net-(IC2-8.DRV)") (class "Default")
      (node (ref "IC2") (pin "8") (pinfunction "8.DRV_8") (pintype "input"))
      (node (ref "R65") (pin "1") (pinfunction "1_1") (pintype "passive"))
    )
    (net (code "46") (name "Net-(IC3-2.MIN_TOFF)") (class "Default")
      (node (ref "IC3") (pin "2") (pinfunction "2.MIN_TOFF_2") (pintype "input"))
      (node (ref "R82") (pin "1") (pinfunction "1_1") (pintype "passive"))
    )
    (net (code "47") (name "Net-(IC3-3.MIN_TON)") (class "Default")
      (node (ref "IC3") (pin "3") (pinfunction "3.MIN_TON_3") (pintype "input"))
      (node (ref "R81") (pin "1") (pinfunction "1_1") (pintype "passive"))
    )
    (net (code "48") (name "Net-(IC3-6.CS)") (class "Default")
      (node (ref "C51") (pin "1") (pinfunction "1_1") (pintype "passive"))
      (node (ref "D13") (pin "C") (pinfunction "C_C") (pintype "passive"))
      (node (ref "IC3") (pin "6") (pinfunction "6.CS_6") (pintype "input"))
      (node (ref "Q7") (pin "D") (pinfunction "D_D") (pintype "passive"))
      (node (ref "TRF1") (pin "10") (pinfunction "13_10") (pintype "passive"))
      (node (ref "TRF1") (pin "21") (pinfunction "13_21") (pintype "passive"))
      (node (ref "TRF1") (pin "22") (pinfunction "12_22") (pintype "passive"))
      (node (ref "TRF1") (pin "29") (pinfunction "12_29") (pintype "passive"))
      (node (ref "TRF1") (pin "30") (pinfunction "13_30") (pintype "passive"))
      (node (ref "TRF1") (pin "43") (pinfunction "12_43") (pintype "passive"))
      (node (ref "TRF1") (pin "44") (pinfunction "13_44") (pintype "passive"))
      (node (ref "TRF1") (pin "9") (pinfunction "12_9") (pintype "passive"))
    )
    (net (code "49") (name "Net-(IC3-8.DRV)") (class "Default")
      (node (ref "IC3") (pin "8") (pinfunction "8.DRV_8") (pintype "input"))
      (node (ref "R83") (pin "1") (pinfunction "1_1") (pintype "passive"))
    )
    (net (code "50") (name "Net-(IC4-CC+)") (class "Default")
      (node (ref "IC4") (pin "3") (pinfunction "CC+_3") (pintype "input"))
      (node (ref "R93") (pin "1") (pinfunction "1_1") (pintype "passive"))
      (node (ref "R95") (pin "2") (pinfunction "2_2") (pintype "passive"))
    )
    (net (code "51") (name "Net-(IC4-CC-)") (class "Default")
      (node (ref "IC4") (pin "2") (pinfunction "CC-_2") (pintype "input"))
      (node (ref "R103") (pin "2") (pinfunction "2_2") (pintype "passive"))
      (node (ref "R99") (pin "1") (pinfunction "1_1") (pintype "passive"))
    )
    (net (code "52") (name "Net-(IC4-CV-)") (class "Default")
      (node (ref "IC4") (pin "4") (pinfunction "CV-_4") (pintype "input"))
      (node (ref "R110") (pin "2") (pinfunction "2_2") (pintype "passive"))
      (node (ref "R114") (pin "1") (pinfunction "1_1") (pintype "passive"))
      (node (ref "R115") (pin "2") (pinfunction "2_2") (pintype "passive"))
    )
    (net (code "53") (name "Net-(IC4-OUT)") (class "Default")
      (node (ref "C85") (pin "2") (pinfunction "2_2") (pintype "passive"))
      (node (ref "C86") (pin "2") (pinfunction "2_2") (pintype "passive"))
      (node (ref "IC4") (pin "7") (pinfunction "OUT_7") (pintype "output"))
      (node (ref "R106") (pin "1") (pinfunction "1_1") (pintype "passive"))
    )
    (net (code "54") (name "Net-(IC4-VCC)") (class "Default")
      (node (ref "C80") (pin "2") (pinfunction "2_2") (pintype "passive"))
      (node (ref "IC4") (pin "8") (pinfunction "VCC_8") (pintype "power_in"))
      (node (ref "R102") (pin "2") (pinfunction "2_2") (pintype "passive"))
    )
    (net (code "55") (name "Net-(IC5A--IN)") (class "Default")
      (node (ref "C87") (pin "1") (pinfunction "1_1") (pintype "passive"))
      (node (ref "IC5") (pin "2") (pinfunction "-IN_2") (pintype "input"))
      (node (ref "R108") (pin "2") (pinfunction "2_2") (pintype "passive"))
      (node (ref "R111") (pin "1") (pinfunction "1_1") (pintype "passive"))
    )
    (net (code "56") (name "Net-(IC5A-OUT)") (class "Default")
      (node (ref "C87") (pin "2") (pinfunction "2_2") (pintype "passive"))
      (node (ref "IC5") (pin "1") (pinfunction "OUT_1") (pintype "output"))
      (node (ref "R111") (pin "2") (pinfunction "2_2") (pintype "passive"))
      (node (ref "R118") (pin "1") (pinfunction "1_1") (pintype "passive"))
    )
    (net (code "57") (name "Net-(IC5B-+IN)") (class "Default")
      (node (ref "IC5") (pin "5") (pinfunction "+IN_5") (pintype "input"))
      (node (ref "R100") (pin "1") (pinfunction "1_1") (pintype "passive"))
    )
    (net (code "58") (name "Net-(IC5B--IN)") (class "Default")
      (node (ref "C84") (pin "1") (pinfunction "1_1") (pintype "passive"))
      (node (ref "IC5") (pin "6") (pinfunction "-IN_6") (pintype "input"))
      (node (ref "R101") (pin "2") (pinfunction "2_2") (pintype "passive"))
      (node (ref "R104") (pin "1") (pinfunction "1_1") (pintype "passive"))
    )
    (net (code "59") (name "Net-(IC8-G4)") (class "Default")
      (node (ref "IC8") (pin "GATE") (pinfunction "G4_GATE") (pintype "passive"))
      (node (ref "Q12") (pin "3") (pinfunction "C_3") (pintype "passive"))
      (node (ref "Q14") (pin "3") (pinfunction "C_3") (pintype "passive"))
      (node (ref "R128") (pin "1") (pinfunction "1_1") (pintype "passive"))
      (node (ref "R146") (pin "2") (pinfunction "2_2") (pintype "passive"))
      (node (ref "Z9") (pin "3") (pinfunction "C_3") (pintype "passive"))
    )
    (net (code "60") (name "Net-(NTC1-1)") (class "Default")
      (node (ref "C1") (pin "1") (pinfunction "1_1") (pintype "passive"))
      (node (ref "C3") (pin "1") (pinfunction "1_1") (pintype "passive"))
      (node (ref "L1") (pin "2") (pinfunction "2_2") (pintype "passive"))
      (node (ref "NTC1") (pin "P$1") (pinfunction "1_P$1") (pintype "passive"))
      (node (ref "VR1") (pin "1") (pinfunction "1_1") (pintype "passive"))
    )
    (net (code "61") (name "Net-(NTC1-2)") (class "Default")
      (node (ref "NTC1") (pin "P$2") (pinfunction "2_P$2") (pintype "passive"))
      (node (ref "X1") (pin "1") (pinfunction "1_1") (pintype "passive"))
    )
    (net (code "62") (name "Net-(OC1-Pad2)") (class "Default")
      (node (ref "OC1") (pin "2") (pinfunction "2_2") (pintype "passive"))
      (node (ref "R106") (pin "2") (pinfunction "2_2") (pintype "passive"))
    )
    (net (code "63") (name "Net-(Q1-B)") (class "Default")
      (node (ref "Q1") (pin "1") (pinfunction "B_1") (pintype "passive"))
      (node (ref "Z2") (pin "1") (pinfunction "A_1") (pintype "passive"))
    )
    (net (code "64") (name "Net-(Q1-C)") (class "Default")
      (node (ref "C12") (pin "1") (pinfunction "1_1") (pintype "passive"))
      (node (ref "Q1") (pin "3") (pinfunction "C_3") (pintype "passive"))
      (node (ref "R8") (pin "1") (pinfunction "1_1") (pintype "passive"))
      (node (ref "R9") (pin "2") (pinfunction "2_2") (pintype "passive"))
    )
    (net (code "65") (name "Net-(Q5-PadG)") (class "Default")
      (node (ref "Q5") (pin "G") (pinfunction "G_G") (pintype "passive"))
      (node (ref "R61") (pin "1") (pinfunction "1_1") (pintype "passive"))
      (node (ref "R65") (pin "2") (pinfunction "2_2") (pintype "passive"))
    )
    (net (code "66") (name "Net-(Q7-PadG)") (class "Default")
      (node (ref "Q7") (pin "G") (pinfunction "G_G") (pintype "passive"))
      (node (ref "R78") (pin "1") (pinfunction "1_1") (pintype "passive"))
      (node (ref "R83") (pin "2") (pinfunction "2_2") (pintype "passive"))
    )
    (net (code "67") (name "Net-(Q10-B)") (class "Default")
      (node (ref "C91") (pin "2") (pinfunction "2_2") (pintype "passive"))
      (node (ref "Q10") (pin "1") (pinfunction "B_1") (pintype "passive"))
      (node (ref "R117") (pin "1") (pinfunction "1_1") (pintype "passive"))
      (node (ref "R119") (pin "2") (pinfunction "2_2") (pintype "passive"))
    )
    (net (code "68") (name "Net-(Q10-C)") (class "Default")
      (node (ref "Q10") (pin "3") (pinfunction "C_3") (pintype "passive"))
      (node (ref "R113") (pin "1") (pinfunction "1_1") (pintype "passive"))
      (node (ref "R114") (pin "2") (pinfunction "2_2") (pintype "passive"))
    )
    (net (code "69") (name "Net-(Q10-E)") (class "Default")
      (node (ref "Q10") (pin "2") (pinfunction "E_2") (pintype "passive"))
      (node (ref "R116") (pin "2") (pinfunction "2_2") (pintype "passive"))
    )
    (net (code "70") (name "Net-(Q11-B)") (class "Default")
      (node (ref "Q11") (pin "1") (pinfunction "B_1") (pintype "passive"))
      (node (ref "R121") (pin "1") (pinfunction "1_1") (pintype "passive"))
      (node (ref "R122") (pin "2") (pinfunction "2_2") (pintype "passive"))
    )
    (net (code "71") (name "Net-(Q11-C)") (class "Default")
      (node (ref "Q11") (pin "3") (pinfunction "C_3") (pintype "passive"))
      (node (ref "R124") (pin "1") (pinfunction "1_1") (pintype "passive"))
      (node (ref "Z6") (pin "3") (pinfunction "C_3") (pintype "passive"))
    )
    (net (code "72") (name "Net-(Q12-B)") (class "Default")
      (node (ref "Q12") (pin "1") (pinfunction "B_1") (pintype "passive"))
      (node (ref "R132") (pin "1") (pinfunction "1_1") (pintype "passive"))
    )
    (net (code "73") (name "Net-(Q13-B)") (class "Default")
      (node (ref "Q13") (pin "1") (pinfunction "B_1") (pintype "passive"))
      (node (ref "R139") (pin "2") (pinfunction "2_2") (pintype "passive"))
      (node (ref "Z8") (pin "1") (pinfunction "A_1") (pintype "passive"))
    )
    (net (code "74") (name "Net-(Q14-B)") (class "Default")
      (node (ref "Q14") (pin "1") (pinfunction "B_1") (pintype "passive"))
      (node (ref "R141") (pin "1") (pinfunction "1_1") (pintype "passive"))
      (node (ref "R142") (pin "1") (pinfunction "1_1") (pintype "passive"))
    )
    (net (code "75") (name "Net-(R1-Pad2)") (class "Default")
      (node (ref "R1") (pin "2") (pinfunction "2_2") (pintype "passive"))
      (node (ref "R2") (pin "1") (pinfunction "1_1") (pintype "passive"))
    )
    (net (code "76") (name "Net-(R5-Pad2)") (class "Default")
      (node (ref "R5") (pin "2") (pinfunction "2_2") (pintype "passive"))
      (node (ref "R6") (pin "1") (pinfunction "1_1") (pintype "passive"))
    )
    (net (code "77") (name "Net-(R17-Pad2)") (class "Default")
      (node (ref "R17") (pin "2") (pinfunction "2_2") (pintype "passive"))
      (node (ref "R19") (pin "1") (pinfunction "1_1") (pintype "passive"))
    )
    (net (code "78") (name "Net-(R18-Pad2)") (class "Default")
      (node (ref "R18") (pin "2") (pinfunction "2_2") (pintype "passive"))
      (node (ref "R20") (pin "1") (pinfunction "1_1") (pintype "passive"))
    )
    (net (code "79") (name "Net-(R33-Pad1)") (class "Default")
      (node (ref "R33") (pin "1") (pinfunction "1_1") (pintype "passive"))
      (node (ref "R34") (pin "2") (pinfunction "2_2") (pintype "passive"))
    )
    (net (code "80") (name "Net-(R34-Pad1)") (class "Default")
      (node (ref "R34") (pin "1") (pinfunction "1_1") (pintype "passive"))
      (node (ref "R35") (pin "2") (pinfunction "2_2") (pintype "passive"))
    )
    (net (code "81") (name "Net-(R35-Pad1)") (class "Default")
      (node (ref "R35") (pin "1") (pinfunction "1_1") (pintype "passive"))
      (node (ref "R36") (pin "2") (pinfunction "2_2") (pintype "passive"))
    )
    (net (code "82") (name "Net-(R36-Pad1)") (class "Default")
      (node (ref "R36") (pin "1") (pinfunction "1_1") (pintype "passive"))
      (node (ref "R37") (pin "2") (pinfunction "2_2") (pintype "passive"))
    )
    (net (code "83") (name "Net-(R38-Pad1)") (class "Default")
      (node (ref "R38") (pin "1") (pinfunction "1_1") (pintype "passive"))
      (node (ref "R39") (pin "2") (pinfunction "2_2") (pintype "passive"))
    )
    (net (code "84") (name "Net-(R39-Pad1)") (class "Default")
      (node (ref "R39") (pin "1") (pinfunction "1_1") (pintype "passive"))
      (node (ref "R40") (pin "2") (pinfunction "2_2") (pintype "passive"))
    )
    (net (code "85") (name "Net-(R40-Pad1)") (class "Default")
      (node (ref "R40") (pin "1") (pinfunction "1_1") (pintype "passive"))
      (node (ref "R41") (pin "2") (pinfunction "2_2") (pintype "passive"))
    )
    (net (code "86") (name "Net-(R42-Pad1)") (class "Default")
      (node (ref "R42") (pin "1") (pinfunction "1_1") (pintype "passive"))
      (node (ref "R43") (pin "2") (pinfunction "2_2") (pintype "passive"))
    )
    (net (code "87") (name "Net-(R88-Pad1)") (class "Default")
      (node (ref "R88") (pin "1") (pinfunction "1_1") (pintype "passive"))
      (node (ref "R90") (pin "2") (pinfunction "2_2") (pintype "passive"))
      (node (ref "R92") (pin "2") (pinfunction "2_2") (pintype "passive"))
      (node (ref "T3") (pin "E") (pinfunction "E_E") (pintype "passive"))
    )
    (net (code "88") (name "Net-(R88-Pad2)") (class "Default")
      (node (ref "R88") (pin "2") (pinfunction "2_2") (pintype "passive"))
      (node (ref "R89") (pin "1") (pinfunction "1_1") (pintype "passive"))
      (node (ref "T3") (pin "B") (pinfunction "B_B") (pintype "passive"))
    )
    (net (code "89") (name "Net-(R90-Pad1)") (class "Default")
      (node (ref "R90") (pin "1") (pinfunction "1_1") (pintype "passive"))
      (node (ref "R91") (pin "1") (pinfunction "1_1") (pintype "passive"))
      (node (ref "T3") (pin "C") (pinfunction "C_C") (pintype "passive"))
    )
    (net (code "90") (name "Net-(R95-Pad1)") (class "Default")
      (node (ref "R95") (pin "1") (pinfunction "1_1") (pintype "passive"))
      (node (ref "R96") (pin "2") (pinfunction "2_2") (pintype "passive"))
    )
    (net (code "91") (name "Net-(R112-Pad1)") (class "Default")
      (node (ref "R112") (pin "1") (pinfunction "1_1") (pintype "passive"))
      (node (ref "R113") (pin "2") (pinfunction "2_2") (pintype "passive"))
    )
    (net (code "92") (name "Net-(R144-Pad2)") (class "Default")
      (node (ref "R144") (pin "2") (pinfunction "2_2") (pintype "passive"))
      (node (ref "T5") (pin "C") (pinfunction "C_C") (pintype "passive"))
    )
    (net (code "93") (name "Net-(T1-B)") (class "Default")
      (node (ref "R4") (pin "2") (pinfunction "2_2") (pintype "passive"))
      (node (ref "T1") (pin "1") (pinfunction "B_1") (pintype "passive"))
      (node (ref "Z1") (pin "3") (pinfunction "C_3") (pintype "passive"))
    )
    (net (code "94") (name "Net-(T1-C)") (class "Default")
      (node (ref "C7") (pin "2") (pinfunction "2_2") (pintype "passive"))
      (node (ref "C9") (pin "2") (pinfunction "2_2") (pintype "passive"))
      (node (ref "D1") (pin "C") (pinfunction "C_C") (pintype "passive"))
      (node (ref "R4") (pin "1") (pinfunction "1_1") (pintype "passive"))
      (node (ref "T1") (pin "4") (pinfunction "C_4") (pintype "passive"))
    )
    (net (code "95") (name "Net-(T1-E)") (class "Default")
      (node (ref "C10") (pin "2") (pinfunction "2_2") (pintype "passive"))
      (node (ref "C11") (pin "2") (pinfunction "2_2") (pintype "passive"))
      (node (ref "D2") (pin "A") (pinfunction "A_A") (pintype "passive"))
      (node (ref "T1") (pin "3") (pinfunction "E_3") (pintype "passive"))
    )
    (net (code "96") (name "Net-(T2-D)") (class "Default")
      (node (ref "R11") (pin "1") (pinfunction "1_1") (pintype "passive"))
      (node (ref "T2") (pin "1") (pinfunction "D_1") (pintype "passive"))
    )
    (net (code "97") (name "Net-(T2-G)") (class "Default")
      (node (ref "R10") (pin "2") (pinfunction "2_2") (pintype "passive"))
      (node (ref "R9") (pin "1") (pinfunction "1_1") (pintype "passive"))
      (node (ref "T2") (pin "3") (pinfunction "G_3") (pintype "passive"))
    )
    (net (code "98") (name "Net-(TRF1-2-Pad1)") (class "Default")
      (node (ref "TRF1") (pin "1") (pinfunction "2_1") (pintype "passive"))
      (node (ref "TRF1") (pin "17") (pinfunction "3_17") (pintype "passive"))
      (node (ref "TRF1") (pin "18") (pinfunction "2_18") (pintype "passive"))
      (node (ref "TRF1") (pin "2") (pinfunction "3_2") (pintype "passive"))
      (node (ref "TRF1") (pin "36") (pinfunction "3_36") (pintype "passive"))
      (node (ref "TRF1") (pin "37") (pinfunction "2_37") (pintype "passive"))
      (node (ref "TRF1") (pin "53") (pinfunction "3_53") (pintype "passive"))
      (node (ref "TRF1") (pin "54") (pinfunction "2_54") (pintype "passive"))
    )
    (net (code "99") (name "Net-(U1-FREQ)") (class "Default")
      (node (ref "R13") (pin "1") (pinfunction "1_1") (pintype "passive"))
      (node (ref "R14") (pin "2") (pinfunction "2_2") (pintype "passive"))
      (node (ref "U1") (pin "4") (pinfunction "FREQ_4") (pintype "bidirectional"))
    )
    (net (code "100") (name "Net-(U1-GATE)") (class "Default")
      (node (ref "D4") (pin "C") (pinfunction "C_C") (pintype "passive"))
      (node (ref "R21") (pin "2") (pinfunction "2_2") (pintype "passive"))
      (node (ref "U1") (pin "8") (pinfunction "GATE_8") (pintype "bidirectional"))
    )
    (net (code "101") (name "Net-(U1-ICOMP)") (class "Default")
      (node (ref "C13") (pin "1") (pinfunction "1_1") (pintype "passive"))
      (node (ref "U1") (pin "2") (pinfunction "ICOMP_2") (pintype "bidirectional"))
    )
    (net (code "102") (name "Net-(U1-ISNS)") (class "Default")
      (node (ref "C14") (pin "1") (pinfunction "1_1") (pintype "passive"))
      (node (ref "R12") (pin "2") (pinfunction "2_2") (pintype "passive"))
      (node (ref "U1") (pin "3") (pinfunction "ISNS_3") (pintype "bidirectional"))
    )
    (net (code "103") (name "Net-(U1-VCOMP)") (class "Default")
      (node (ref "C18") (pin "1") (pinfunction "1_1") (pintype "passive"))
      (node (ref "R15") (pin "2") (pinfunction "2_2") (pintype "passive"))
      (node (ref "U1") (pin "5") (pinfunction "VCOMP_5") (pintype "bidirectional"))
    )
    (net (code "104") (name "Net-(U2-P1)") (class "Default")
      (node (ref "B1") (pin "+") (pinfunction "+_+") (pintype "passive"))
      (node (ref "C8") (pin "1") (pinfunction "1_1") (pintype "passive"))
      (node (ref "D3") (pin "A") (pinfunction "A_A") (pintype "passive"))
      (node (ref "R13") (pin "2") (pinfunction "2_2") (pintype "passive"))
      (node (ref "R5") (pin "1") (pinfunction "1_1") (pintype "passive"))
      (node (ref "U2") (pin "1") (pinfunction "P1_1") (pintype "passive"))
    )
    (net (code "105") (name "Net-(U2-P2)") (class "Default")
      (node (ref "C20") (pin "1") (pinfunction "1_1") (pintype "passive"))
      (node (ref "D5") (pin "A") (pinfunction "A_A") (pintype "passive"))
      (node (ref "Q2") (pin "D") (pinfunction "D_D") (pintype "passive"))
      (node (ref "R23") (pin "1") (pinfunction "1_1") (pintype "passive"))
      (node (ref "R25") (pin "1") (pinfunction "1_1") (pintype "passive"))
      (node (ref "R26") (pin "1") (pinfunction "1_1") (pintype "passive"))
      (node (ref "R30") (pin "1") (pinfunction "1_1") (pintype "passive"))
      (node (ref "U2") (pin "2") (pinfunction "P2_2") (pintype "passive"))
    )
    (net (code "106") (name "Net-(U3-FB)") (class "Default")
      (node (ref "C23") (pin "1") (pinfunction "1_1") (pintype "passive"))
      (node (ref "OC1") (pin "4") (pinfunction "4_4") (pintype "passive"))
      (node (ref "OC2") (pin "4") (pinfunction "4_4") (pintype "passive"))
      (node (ref "R24") (pin "2") (pinfunction "2_2") (pintype "passive"))
      (node (ref "U3") (pin "5") (pinfunction "FB_5") (pintype "input"))
    )
    (net (code "107") (name "Net-(U3-HB)") (class "Default")
      (node (ref "C35") (pin "2") (pinfunction "2_2") (pintype "passive"))
      (node (ref "D10") (pin "C") (pinfunction "C_C") (pintype "passive"))
      (node (ref "U3") (pin "14") (pinfunction "HB_14") (pintype "bidirectional"))
    )
    (net (code "108") (name "Net-(U3-HO)") (class "Default")
      (node (ref "R45") (pin "1") (pinfunction "1_1") (pintype "passive"))
      (node (ref "R47") (pin "1") (pinfunction "1_1") (pintype "passive"))
      (node (ref "U3") (pin "15") (pinfunction "HO_15") (pintype "output"))
    )
    (net (code "109") (name "Net-(U3-HV)") (class "Default")
      (node (ref "R32") (pin "1") (pinfunction "1_1") (pintype "passive"))
      (node (ref "U3") (pin "1") (pinfunction "HV_1") (pintype "input"))
    )
    (net (code "110") (name "Net-(U3-LL{slash}SS)") (class "Default")
      (node (ref "C32") (pin "1") (pinfunction "1_1") (pintype "passive"))
      (node (ref "R48") (pin "2") (pinfunction "2_2") (pintype "passive"))
      (node (ref "R49") (pin "1") (pinfunction "1_1") (pintype "passive"))
      (node (ref "U3") (pin "9") (pinfunction "LL/SS_9") (pintype "input"))
    )
    (net (code "111") (name "Net-(U3-LO)") (class "Default")
      (node (ref "R44") (pin "1") (pinfunction "1_1") (pintype "passive"))
      (node (ref "R46") (pin "1") (pinfunction "1_1") (pintype "passive"))
      (node (ref "U3") (pin "10") (pinfunction "LO_10") (pintype "output"))
    )
    (net (code "112") (name "Net-(U4-P2)") (class "Default")
      (node (ref "TRF1") (pin "16") (pinfunction "4_16") (pintype "passive"))
      (node (ref "TRF1") (pin "3") (pinfunction "4_3") (pintype "passive"))
      (node (ref "TRF1") (pin "35") (pinfunction "4_35") (pintype "passive"))
      (node (ref "TRF1") (pin "52") (pinfunction "4_52") (pintype "passive"))
      (node (ref "U4") (pin "2") (pinfunction "P2_2") (pintype "passive"))
    )
    (net (code "113") (name "Net-(X1B-1)") (class "Default")
      (node (ref "F1") (pin "1") (pinfunction "1_1") (pintype "passive"))
      (node (ref "X1") (pin "2") (pinfunction "1_2") (pintype "passive"))
    )
    (net (code "114") (name "Net-(Z2-C)") (class "Default")
      (node (ref "R6") (pin "2") (pinfunction "2_2") (pintype "passive"))
      (node (ref "R7") (pin "2") (pinfunction "2_2") (pintype "passive"))
      (node (ref "Z2") (pin "3") (pinfunction "C_3") (pintype "passive"))
    )
    (net (code "115") (name "Net-(Z3-A)") (class "Default")
      (node (ref "R24") (pin "1") (pinfunction "1_1") (pintype "passive"))
      (node (ref "Z3") (pin "1") (pinfunction "A_1") (pintype "passive"))
    )
    (net (code "116") (name "Net-(Z5-A)") (class "Default")
      (node (ref "R123") (pin "2") (pinfunction "2_2") (pintype "passive"))
      (node (ref "Z5") (pin "1") (pinfunction "A_1") (pintype "passive"))
    )
    (net (code "117") (name "Net-(Z5-C)") (class "Default")
      (node (ref "OC2") (pin "2") (pinfunction "2_2") (pintype "passive"))
      (node (ref "Z5") (pin "3") (pinfunction "C_3") (pintype "passive"))
    )
    (net (code "118") (name "Net-(Z8-C)") (class "Default")
      (node (ref "R140") (pin "1") (pinfunction "1_1") (pintype "passive"))
      (node (ref "R144") (pin "1") (pinfunction "1_1") (pintype "passive"))
      (node (ref "Z8") (pin "3") (pinfunction "C_3") (pintype "passive"))
    )
    (net (code "119") (name "OUTPUT_REVERSE") (class "Default")
      (node (ref "JP5") (pin "12") (pinfunction "12_12") (pintype "passive"))
      (node (ref "Q13") (pin "3") (pinfunction "C_3") (pintype "passive"))
    )
    (net (code "120") (name "OVER_VOLT") (class "Default")
      (node (ref "JP5") (pin "8") (pinfunction "8_8") (pintype "passive"))
      (node (ref "R121") (pin "2") (pinfunction "2_2") (pintype "passive"))
    )
    (net (code "121") (name "PE") (class "Default")
      (node (ref "C1") (pin "2") (pinfunction "2_2") (pintype "passive"))
      (node (ref "C110") (pin "2") (pinfunction "2_2") (pintype "passive"))
      (node (ref "C111") (pin "2") (pinfunction "2_2") (pintype "passive"))
      (node (ref "C112") (pin "1") (pinfunction "1_1") (pintype "passive"))
      (node (ref "C2") (pin "2") (pinfunction "2_2") (pintype "passive"))
      (node (ref "C5") (pin "2") (pinfunction "2_2") (pintype "passive"))
      (node (ref "C53") (pin "2") (pinfunction "2_2") (pintype "passive"))
      (node (ref "C58") (pin "2") (pinfunction "2_2") (pintype "passive"))
      (node (ref "C58") (pin "4") (pinfunction "2_4") (pintype "passive"))
      (node (ref "C6") (pin "2") (pinfunction "2_2") (pintype "passive"))
      (node (ref "C90") (pin "1") (pinfunction "1_1") (pintype "passive"))
      (node (ref "X1") (pin "3") (pinfunction "1_3") (pintype "passive"))
    )
    (net (code "122") (name "RVCC_12V") (class "Default")
      (node (ref "C15") (pin "1") (pinfunction "1_1") (pintype "passive"))
      (node (ref "C17") (pin "1") (pinfunction "1_1") (pintype "passive"))
      (node (ref "R48") (pin "1") (pinfunction "1_1") (pintype "passive"))
      (node (ref "R50") (pin "1") (pinfunction "1_1") (pintype "passive"))
      (node (ref "R8") (pin "2") (pinfunction "2_2") (pintype "passive"))
      (node (ref "U1") (pin "7") (pinfunction "VCC_7") (pintype "bidirectional"))
      (node (ref "U3") (pin "12") (pinfunction "RVCC_12") (pintype "output"))
      (node (ref "Z3") (pin "3") (pinfunction "C_3") (pintype "passive"))
    )
    (net (code "123") (name "VAC_AUX") (class "Default")
      (node (ref "D1") (pin "A") (pinfunction "A_A") (pintype "passive"))
      (node (ref "R1") (pin "1") (pinfunction "1_1") (pintype "passive"))
      (node (ref "TRF1") (pin "15") (pinfunction "6_15") (pintype "passive"))
      (node (ref "TRF1") (pin "34") (pinfunction "6_34") (pintype "passive"))
      (node (ref "TRF1") (pin "5") (pinfunction "6_5") (pintype "passive"))
      (node (ref "TRF1") (pin "50") (pinfunction "6_50") (pintype "passive"))
    )
    (net (code "124") (name "VCC") (class "Default")
      (node (ref "C26") (pin "+") (pinfunction "+_+") (pintype "passive"))
      (node (ref "C27") (pin "1") (pinfunction "1_1") (pintype "passive"))
      (node (ref "D2") (pin "C") (pinfunction "C_C") (pintype "passive"))
      (node (ref "U3") (pin "3") (pinfunction "VCC_3") (pintype "power_in"))
    )
    (net (code "125") (name "VCR") (class "Default")
      (node (ref "C28") (pin "1") (pinfunction "1_1") (pintype "passive"))
      (node (ref "C30") (pin "1") (pinfunction "1_1") (pintype "passive"))
      (node (ref "C36") (pin "2") (pinfunction "2_2") (pintype "passive"))
      (node (ref "U3") (pin "7") (pinfunction "VCR_7") (pintype "input"))
    )
    (net (code "126") (name "VSENSE") (class "Default")
      (node (ref "C19") (pin "1") (pinfunction "1_1") (pintype "passive"))
      (node (ref "R11") (pin "2") (pinfunction "2_2") (pintype "passive"))
      (node (ref "R16") (pin "2") (pinfunction "2_2") (pintype "passive"))
      (node (ref "R37") (pin "1") (pinfunction "1_1") (pintype "passive"))
      (node (ref "U1") (pin "6") (pinfunction "VSNS_6") (pintype "bidirectional"))
    )
    (net (code "127") (name "V_PWM") (class "Default")
      (node (ref "JP5") (pin "2") (pinfunction "2_2") (pintype "passive"))
      (node (ref "R119") (pin "1") (pinfunction "1_1") (pintype "passive"))
    )
  )
)
